# Microcontroller.net
KiCad netlist of a schematic drawn in Altium Designer
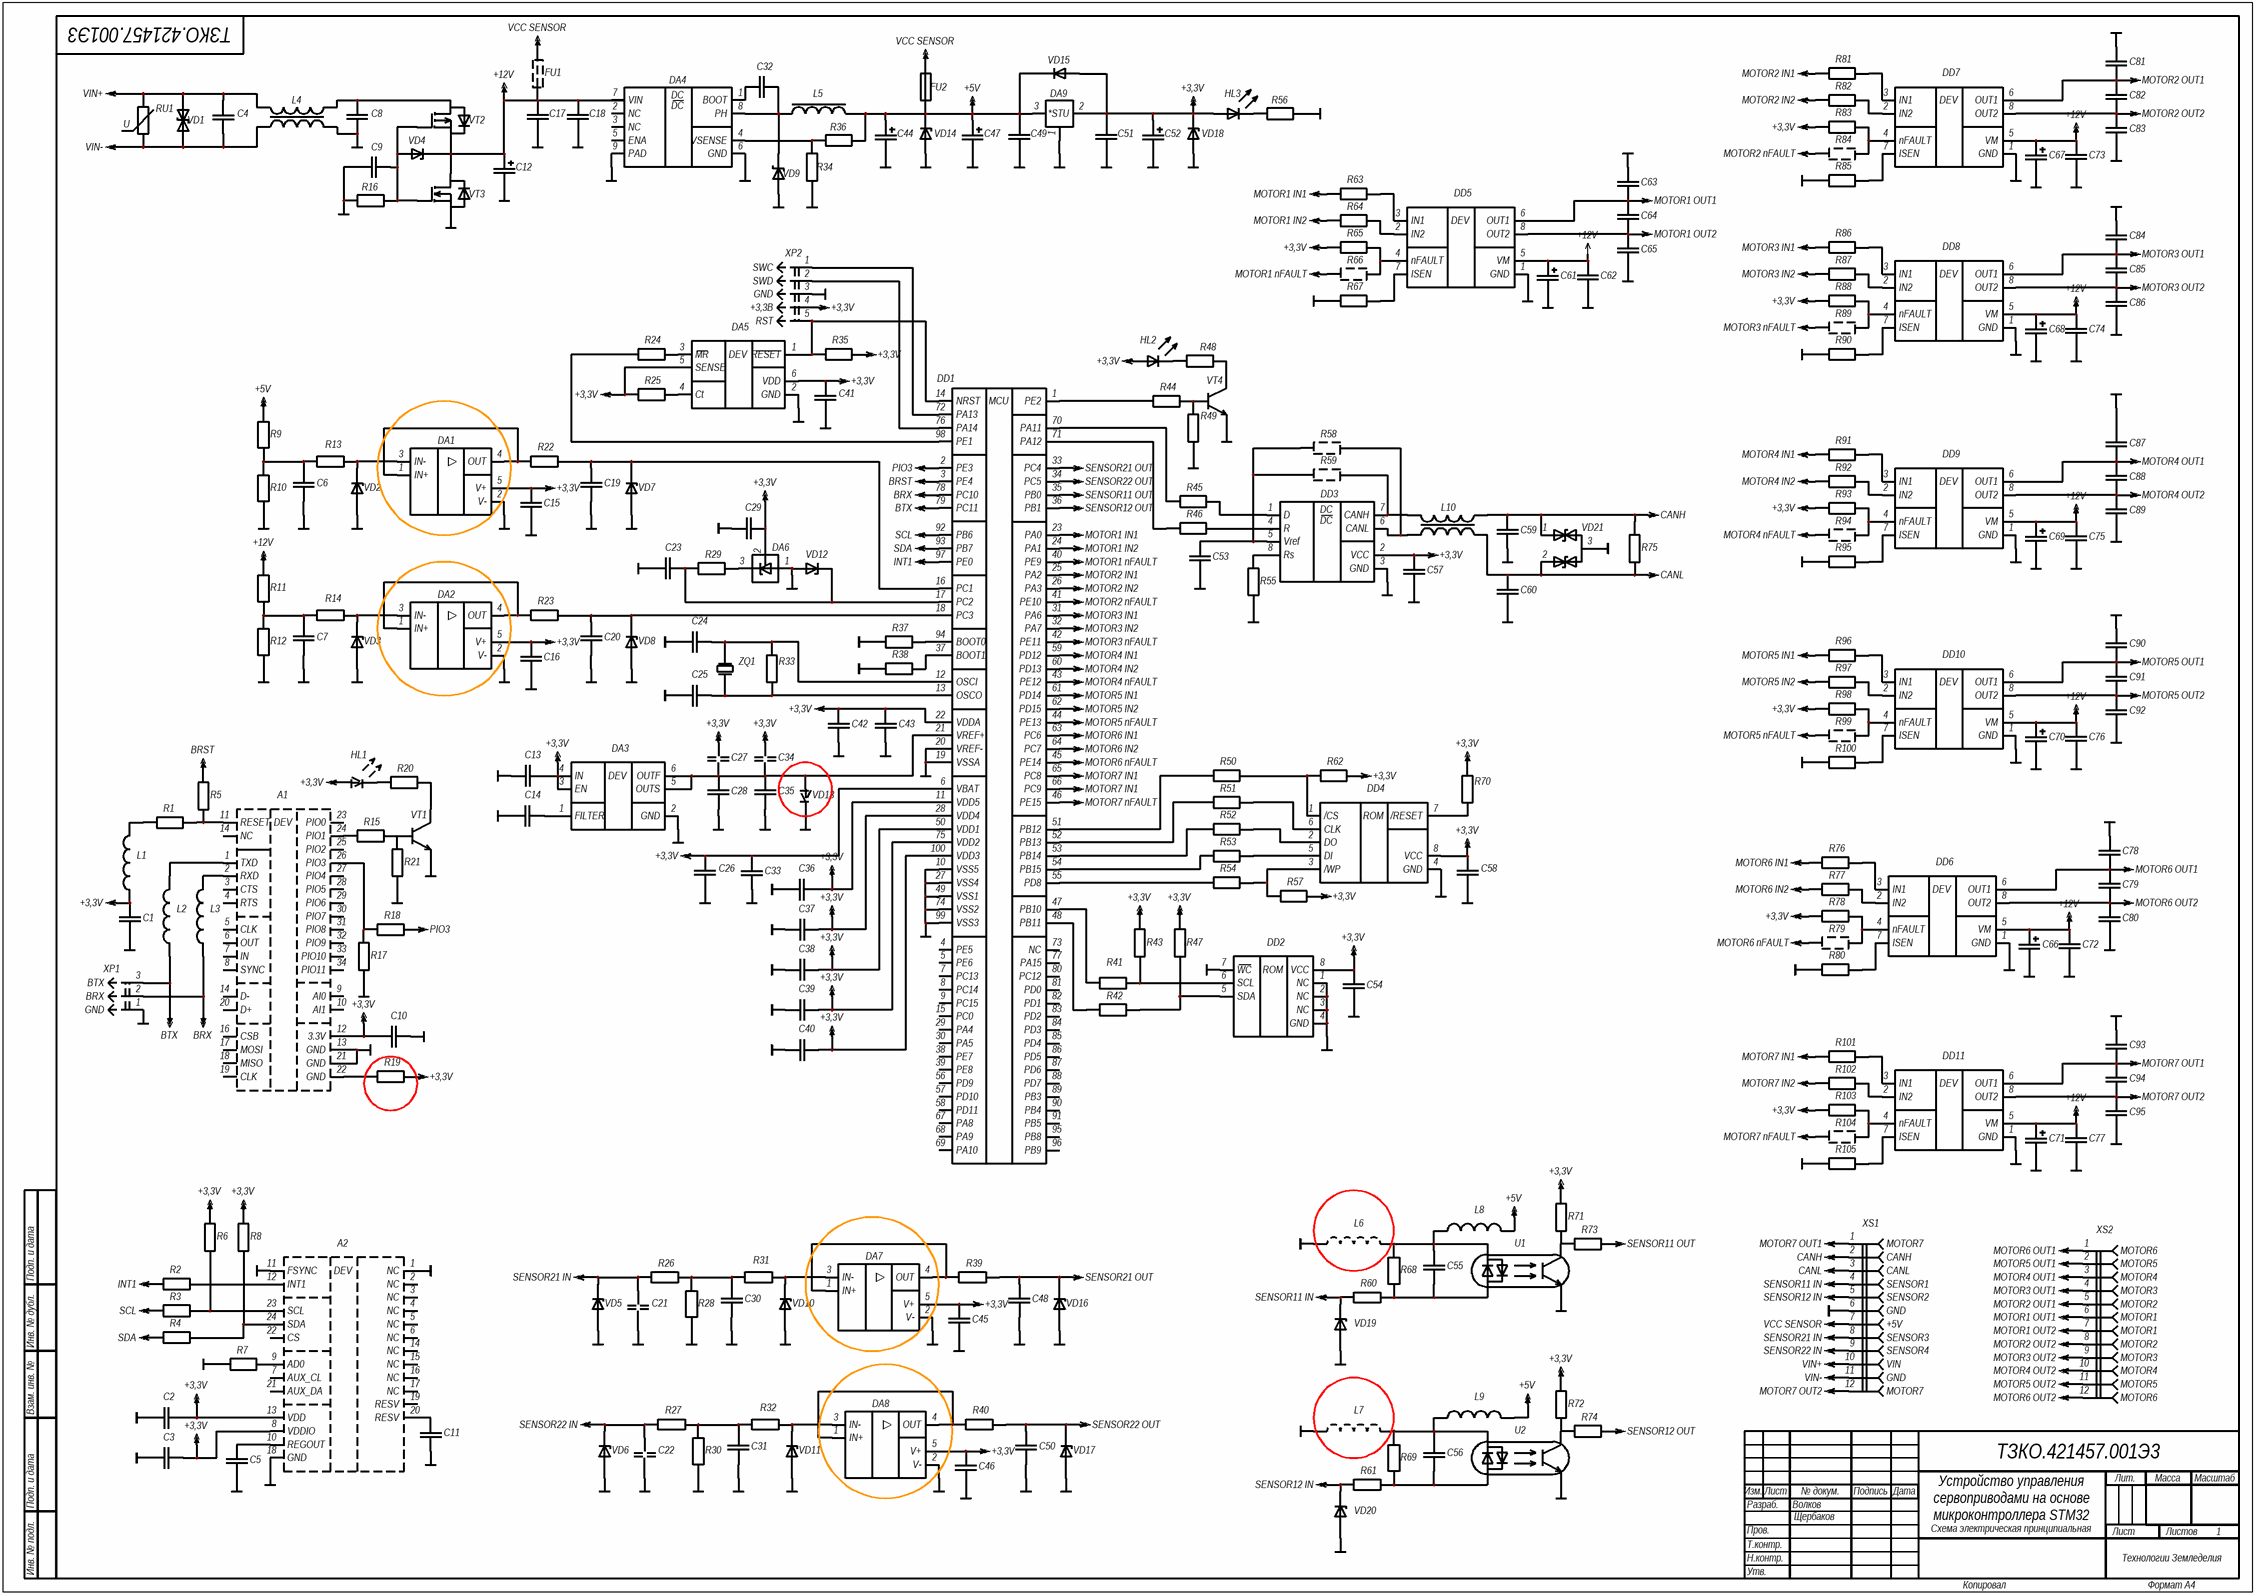
[diagram p0: Microcontroller.SchDoc]

(export (version "E")
  (design (tool "Eeschema 10.0.6"))
  (components
    (comp (ref "A1")
      (value "HC-06")
      (description "34 pin 3,3V not installed")
      (libsource (lib "Library") (part "Device_Bluetooth_HC-06_Not_Installed"))
    )
    (comp (ref "A2")
      (value "ICM-20948")
      (description "24 pin 3,3V not installed")
      (libsource (lib "Library") (part "Device_Gyroscope_Accelerometer_ICM-20948_Not_Installed"))
    )
    (comp (ref "C1")
      (value "Capacitor_Fixed")
      (description "2 pin")
      (libsource (lib "Library") (part "Capacitor_Fixed"))
    )
    (comp (ref "C2")
      (value "Capacitor_Fixed")
      (description "2 pin")
      (libsource (lib "Library") (part "Capacitor_Fixed"))
    )
    (comp (ref "C3")
      (value "Capacitor_Fixed")
      (description "2 pin")
      (libsource (lib "Library") (part "Capacitor_Fixed"))
    )
    (comp (ref "C4")
      (value "Capacitor_Fixed")
      (description "2 pin")
      (libsource (lib "Library") (part "Capacitor_Fixed"))
    )
    (comp (ref "C5")
      (value "Capacitor_Fixed")
      (description "2 pin")
      (libsource (lib "Library") (part "Capacitor_Fixed"))
    )
    (comp (ref "C6")
      (value "Capacitor_Fixed")
      (description "2 pin")
      (libsource (lib "Library") (part "Capacitor_Fixed"))
    )
    (comp (ref "C7")
      (value "Capacitor_Fixed")
      (description "2 pin")
      (libsource (lib "Library") (part "Capacitor_Fixed"))
    )
    (comp (ref "C8")
      (value "Capacitor_Fixed")
      (description "2 pin")
      (libsource (lib "Library") (part "Capacitor_Fixed"))
    )
    (comp (ref "C9")
      (value "Capacitor_Fixed")
      (description "2 pin")
      (libsource (lib "Library") (part "Capacitor_Fixed"))
    )
    (comp (ref "C10")
      (value "Capacitor_Fixed")
      (description "2 pin")
      (libsource (lib "Library") (part "Capacitor_Fixed"))
    )
    (comp (ref "C11")
      (value "Capacitor_Fixed")
      (description "2 pin")
      (libsource (lib "Library") (part "Capacitor_Fixed"))
    )
    (comp (ref "C12")
      (value "Capacitor_Polarized")
      (description "2 pin")
      (libsource (lib "Library") (part "Capacitor_Polarized"))
    )
    (comp (ref "C13")
      (value "Capacitor_Fixed")
      (description "2 pin")
      (libsource (lib "Library") (part "Capacitor_Fixed"))
    )
    (comp (ref "C14")
      (value "Capacitor_Fixed")
      (description "2 pin")
      (libsource (lib "Library") (part "Capacitor_Fixed"))
    )
    (comp (ref "C15")
      (value "Capacitor_Fixed")
      (description "2 pin")
      (libsource (lib "Library") (part "Capacitor_Fixed"))
    )
    (comp (ref "C16")
      (value "Capacitor_Fixed")
      (description "2 pin")
      (libsource (lib "Library") (part "Capacitor_Fixed"))
    )
    (comp (ref "C17")
      (value "Capacitor_Fixed")
      (description "2 pin")
      (libsource (lib "Library") (part "Capacitor_Fixed"))
    )
    (comp (ref "C18")
      (value "Capacitor_Fixed")
      (description "2 pin")
      (libsource (lib "Library") (part "Capacitor_Fixed"))
    )
    (comp (ref "C19")
      (value "Capacitor_Fixed")
      (description "2 pin")
      (libsource (lib "Library") (part "Capacitor_Fixed"))
    )
    (comp (ref "C20")
      (value "Capacitor_Fixed")
      (description "2 pin")
      (libsource (lib "Library") (part "Capacitor_Fixed"))
    )
    (comp (ref "C21")
      (value "Capacitor_Fixed_Not_Installed")
      (description "2 pin not installed")
      (libsource (lib "Library") (part "Capacitor_Fixed_Not_Installed"))
    )
    (comp (ref "C22")
      (value "Capacitor_Fixed_Not_Installed")
      (description "2 pin not installed")
      (libsource (lib "Library") (part "Capacitor_Fixed_Not_Installed"))
    )
    (comp (ref "C23")
      (value "Capacitor_Fixed")
      (description "2 pin")
      (libsource (lib "Library") (part "Capacitor_Fixed"))
    )
    (comp (ref "C24")
      (value "Capacitor_Fixed")
      (description "2 pin")
      (libsource (lib "Library") (part "Capacitor_Fixed"))
    )
    (comp (ref "C25")
      (value "Capacitor_Fixed")
      (description "2 pin")
      (libsource (lib "Library") (part "Capacitor_Fixed"))
    )
    (comp (ref "C26")
      (value "Capacitor_Fixed")
      (description "2 pin")
      (libsource (lib "Library") (part "Capacitor_Fixed"))
    )
    (comp (ref "C27")
      (value "Capacitor_Fixed_Not_Installed")
      (description "2 pin not installed")
      (libsource (lib "Library") (part "Capacitor_Fixed_Not_Installed"))
    )
    (comp (ref "C28")
      (value "Capacitor_Fixed")
      (description "2 pin")
      (libsource (lib "Library") (part "Capacitor_Fixed"))
    )
    (comp (ref "C29")
      (value "Capacitor_Fixed")
      (description "2 pin")
      (libsource (lib "Library") (part "Capacitor_Fixed"))
    )
    (comp (ref "C30")
      (value "Capacitor_Fixed")
      (description "2 pin")
      (libsource (lib "Library") (part "Capacitor_Fixed"))
    )
    (comp (ref "C31")
      (value "Capacitor_Fixed")
      (description "2 pin")
      (libsource (lib "Library") (part "Capacitor_Fixed"))
    )
    (comp (ref "C32")
      (value "Capacitor_Fixed")
      (description "2 pin")
      (libsource (lib "Library") (part "Capacitor_Fixed"))
    )
    (comp (ref "C33")
      (value "Capacitor_Fixed")
      (description "2 pin")
      (libsource (lib "Library") (part "Capacitor_Fixed"))
    )
    (comp (ref "C34")
      (value "Capacitor_Fixed_Not_Installed")
      (description "2 pin not installed")
      (libsource (lib "Library") (part "Capacitor_Fixed_Not_Installed"))
    )
    (comp (ref "C35")
      (value "Capacitor_Fixed")
      (description "2 pin")
      (libsource (lib "Library") (part "Capacitor_Fixed"))
    )
    (comp (ref "C36")
      (value "Capacitor_Fixed")
      (description "2 pin")
      (libsource (lib "Library") (part "Capacitor_Fixed"))
    )
    (comp (ref "C37")
      (value "Capacitor_Fixed")
      (description "2 pin")
      (libsource (lib "Library") (part "Capacitor_Fixed"))
    )
    (comp (ref "C38")
      (value "Capacitor_Fixed")
      (description "2 pin")
      (libsource (lib "Library") (part "Capacitor_Fixed"))
    )
    (comp (ref "C39")
      (value "Capacitor_Fixed")
      (description "2 pin")
      (libsource (lib "Library") (part "Capacitor_Fixed"))
    )
    (comp (ref "C40")
      (value "Capacitor_Fixed")
      (description "2 pin")
      (libsource (lib "Library") (part "Capacitor_Fixed"))
    )
    (comp (ref "C41")
      (value "Capacitor_Fixed")
      (description "2 pin")
      (libsource (lib "Library") (part "Capacitor_Fixed"))
    )
    (comp (ref "C42")
      (value "Capacitor_Fixed")
      (description "2 pin")
      (libsource (lib "Library") (part "Capacitor_Fixed"))
    )
    (comp (ref "C43")
      (value "Capacitor_Fixed")
      (description "2 pin")
      (libsource (lib "Library") (part "Capacitor_Fixed"))
    )
    (comp (ref "C44")
      (value "Capacitor_Polarized")
      (description "2 pin")
      (libsource (lib "Library") (part "Capacitor_Polarized"))
    )
    (comp (ref "C45")
      (value "Capacitor_Fixed")
      (description "2 pin")
      (libsource (lib "Library") (part "Capacitor_Fixed"))
    )
    (comp (ref "C46")
      (value "Capacitor_Fixed")
      (description "2 pin")
      (libsource (lib "Library") (part "Capacitor_Fixed"))
    )
    (comp (ref "C47")
      (value "Capacitor_Polarized")
      (description "2 pin")
      (libsource (lib "Library") (part "Capacitor_Polarized"))
    )
    (comp (ref "C48")
      (value "Capacitor_Fixed")
      (description "2 pin")
      (libsource (lib "Library") (part "Capacitor_Fixed"))
    )
    (comp (ref "C49")
      (value "Capacitor_Fixed")
      (description "2 pin")
      (libsource (lib "Library") (part "Capacitor_Fixed"))
    )
    (comp (ref "C50")
      (value "Capacitor_Fixed")
      (description "2 pin")
      (libsource (lib "Library") (part "Capacitor_Fixed"))
    )
    (comp (ref "C51")
      (value "Capacitor_Fixed")
      (description "2 pin")
      (libsource (lib "Library") (part "Capacitor_Fixed"))
    )
    (comp (ref "C52")
      (value "Capacitor_Polarized")
      (description "2 pin")
      (libsource (lib "Library") (part "Capacitor_Polarized"))
    )
    (comp (ref "C53")
      (value "Capacitor_Fixed")
      (description "2 pin")
      (libsource (lib "Library") (part "Capacitor_Fixed"))
    )
    (comp (ref "C54")
      (value "Capacitor_Fixed")
      (description "2 pin")
      (libsource (lib "Library") (part "Capacitor_Fixed"))
    )
    (comp (ref "C55")
      (value "Capacitor_Fixed")
      (description "2 pin")
      (libsource (lib "Library") (part "Capacitor_Fixed"))
    )
    (comp (ref "C56")
      (value "Capacitor_Fixed")
      (description "2 pin")
      (libsource (lib "Library") (part "Capacitor_Fixed"))
    )
    (comp (ref "C57")
      (value "Capacitor_Fixed")
      (description "2 pin")
      (libsource (lib "Library") (part "Capacitor_Fixed"))
    )
    (comp (ref "C58")
      (value "Capacitor_Fixed")
      (description "2 pin")
      (libsource (lib "Library") (part "Capacitor_Fixed"))
    )
    (comp (ref "C59")
      (value "Capacitor_Fixed")
      (description "2 pin")
      (libsource (lib "Library") (part "Capacitor_Fixed"))
    )
    (comp (ref "C60")
      (value "Capacitor_Fixed")
      (description "2 pin")
      (libsource (lib "Library") (part "Capacitor_Fixed"))
    )
    (comp (ref "C61")
      (value "Capacitor_Polarized")
      (description "2 pin")
      (libsource (lib "Library") (part "Capacitor_Polarized"))
    )
    (comp (ref "C62")
      (value "Capacitor_Fixed")
      (description "2 pin")
      (libsource (lib "Library") (part "Capacitor_Fixed"))
    )
    (comp (ref "C63")
      (value "Capacitor_Fixed")
      (description "2 pin")
      (libsource (lib "Library") (part "Capacitor_Fixed"))
    )
    (comp (ref "C64")
      (value "Capacitor_Fixed")
      (description "2 pin")
      (libsource (lib "Library") (part "Capacitor_Fixed"))
    )
    (comp (ref "C65")
      (value "Capacitor_Fixed")
      (description "2 pin")
      (libsource (lib "Library") (part "Capacitor_Fixed"))
    )
    (comp (ref "C66")
      (value "Capacitor_Polarized")
      (description "2 pin")
      (libsource (lib "Library") (part "Capacitor_Polarized"))
    )
    (comp (ref "C67")
      (value "Capacitor_Polarized")
      (description "2 pin")
      (libsource (lib "Library") (part "Capacitor_Polarized"))
    )
    (comp (ref "C68")
      (value "Capacitor_Polarized")
      (description "2 pin")
      (libsource (lib "Library") (part "Capacitor_Polarized"))
    )
    (comp (ref "C69")
      (value "Capacitor_Polarized")
      (description "2 pin")
      (libsource (lib "Library") (part "Capacitor_Polarized"))
    )
    (comp (ref "C70")
      (value "Capacitor_Polarized")
      (description "2 pin")
      (libsource (lib "Library") (part "Capacitor_Polarized"))
    )
    (comp (ref "C71")
      (value "Capacitor_Polarized")
      (description "2 pin")
      (libsource (lib "Library") (part "Capacitor_Polarized"))
    )
    (comp (ref "C72")
      (value "Capacitor_Fixed")
      (description "2 pin")
      (libsource (lib "Library") (part "Capacitor_Fixed"))
    )
    (comp (ref "C73")
      (value "Capacitor_Fixed")
      (description "2 pin")
      (libsource (lib "Library") (part "Capacitor_Fixed"))
    )
    (comp (ref "C74")
      (value "Capacitor_Fixed")
      (description "2 pin")
      (libsource (lib "Library") (part "Capacitor_Fixed"))
    )
    (comp (ref "C75")
      (value "Capacitor_Fixed")
      (description "2 pin")
      (libsource (lib "Library") (part "Capacitor_Fixed"))
    )
    (comp (ref "C76")
      (value "Capacitor_Fixed")
      (description "2 pin")
      (libsource (lib "Library") (part "Capacitor_Fixed"))
    )
    (comp (ref "C77")
      (value "Capacitor_Fixed")
      (description "2 pin")
      (libsource (lib "Library") (part "Capacitor_Fixed"))
    )
    (comp (ref "C78")
      (value "Capacitor_Fixed")
      (description "2 pin")
      (libsource (lib "Library") (part "Capacitor_Fixed"))
    )
    (comp (ref "C79")
      (value "Capacitor_Fixed")
      (description "2 pin")
      (libsource (lib "Library") (part "Capacitor_Fixed"))
    )
    (comp (ref "C80")
      (value "Capacitor_Fixed")
      (description "2 pin")
      (libsource (lib "Library") (part "Capacitor_Fixed"))
    )
    (comp (ref "C81")
      (value "Capacitor_Fixed")
      (description "2 pin")
      (libsource (lib "Library") (part "Capacitor_Fixed"))
    )
    (comp (ref "C82")
      (value "Capacitor_Fixed")
      (description "2 pin")
      (libsource (lib "Library") (part "Capacitor_Fixed"))
    )
    (comp (ref "C83")
      (value "Capacitor_Fixed")
      (description "2 pin")
      (libsource (lib "Library") (part "Capacitor_Fixed"))
    )
    (comp (ref "C84")
      (value "Capacitor_Fixed")
      (description "2 pin")
      (libsource (lib "Library") (part "Capacitor_Fixed"))
    )
    (comp (ref "C85")
      (value "Capacitor_Fixed")
      (description "2 pin")
      (libsource (lib "Library") (part "Capacitor_Fixed"))
    )
    (comp (ref "C86")
      (value "Capacitor_Fixed")
      (description "2 pin")
      (libsource (lib "Library") (part "Capacitor_Fixed"))
    )
    (comp (ref "C87")
      (value "Capacitor_Fixed")
      (description "2 pin")
      (libsource (lib "Library") (part "Capacitor_Fixed"))
    )
    (comp (ref "C88")
      (value "Capacitor_Fixed")
      (description "2 pin")
      (libsource (lib "Library") (part "Capacitor_Fixed"))
    )
    (comp (ref "C89")
      (value "Capacitor_Fixed")
      (description "2 pin")
      (libsource (lib "Library") (part "Capacitor_Fixed"))
    )
    (comp (ref "C90")
      (value "Capacitor_Fixed")
      (description "2 pin")
      (libsource (lib "Library") (part "Capacitor_Fixed"))
    )
    (comp (ref "C91")
      (value "Capacitor_Fixed")
      (description "2 pin")
      (libsource (lib "Library") (part "Capacitor_Fixed"))
    )
    (comp (ref "C92")
      (value "Capacitor_Fixed")
      (description "2 pin")
      (libsource (lib "Library") (part "Capacitor_Fixed"))
    )
    (comp (ref "C93")
      (value "Capacitor_Fixed")
      (description "2 pin")
      (libsource (lib "Library") (part "Capacitor_Fixed"))
    )
    (comp (ref "C94")
      (value "Capacitor_Fixed")
      (description "2 pin")
      (libsource (lib "Library") (part "Capacitor_Fixed"))
    )
    (comp (ref "C95")
      (value "Capacitor_Fixed")
      (description "2 pin")
      (libsource (lib "Library") (part "Capacitor_Fixed"))
    )
    (comp (ref "DA1")
      (value "OPA348AIDBVR")
      (description "5 pin 3,3V")
      (libsource (lib "Library") (part "Microcircuit_Analog_Operational_Amplifier_OPA348AIDBVR"))
    )
    (comp (ref "DA2")
      (value "OPA348AIDBVR")
      (description "5 pin 3,3V")
      (libsource (lib "Library") (part "Microcircuit_Analog_Operational_Amplifier_OPA348AIDBVR"))
    )
    (comp (ref "DA3")
      (value "MAX6070BAUT12+T")
      (description "6 pin 3,3V")
      (libsource (lib "Library") (part "Microcircuit_Analog_Reference_Voltage_Source_MAX6070BAUT12+T"))
    )
    (comp (ref "DA4")
      (value "TPS5430DDAR")
      (description "8 pin + pad from 12V to 5V")
      (libsource (lib "Library") (part "Microcircuit_Analog_DC_DC_Converter_TPS5430"))
    )
    (comp (ref "DA5")
      (value "TPS3808G33DBVR")
      (description "6 pin 3,3V")
      (libsource (lib "Library") (part "Microcircuit_Analog_Power_Monitor_TPS3808G33DBVR"))
    )
    (comp (ref "DA6")
      (value "TL431")
      (description "3 pin")
      (libsource (lib "Library") (part "Microcircuit_Analog_Reference_Power_Supply_TL431"))
    )
    (comp (ref "DA7")
      (value "OPA348AIDBVR")
      (description "5 pin 3,3V")
      (libsource (lib "Library") (part "Microcircuit_Analog_Operational_Amplifier_OPA348AIDBVR"))
    )
    (comp (ref "DA8")
      (value "OPA348AIDBVR")
      (description "5 pin 3,3V")
      (libsource (lib "Library") (part "Microcircuit_Analog_Operational_Amplifier_OPA348AIDBVR"))
    )
    (comp (ref "DA9")
      (value "LM1117MP")
      (description "3 pin from 5V to 3,3V")
      (libsource (lib "Library") (part "Microcircuit_Analog_Linear_Stabilizer_LM1117MP"))
    )
    (comp (ref "DD1")
      (value "STM32F103VET6")
      (description "100 pin 3,3V")
      (libsource (lib "Library") (part "Microcircuit_Digital_Microcontroller_STM32VET6"))
    )
    (comp (ref "DD2")
      (value "M24256E-FMN6TP")
      (description "8 pin 3,3V")
      (libsource (lib "Library") (part "Microcircuit_Digital_Memory_EEPROM_M24256E-FMN6TP"))
    )
    (comp (ref "DD3")
      (value "VP230")
      (description "8 pin 3,3V")
      (libsource (lib "Library") (part "Microcircuit_Digital_Transceiver_UART_CAN"))
    )
    (comp (ref "DD4")
      (value "W25Q64JVSSIQ")
      (description "8 pin 3,3V")
      (libsource (lib "Library") (part "Microcircuit_Digital_Memory_Flash_W25Q64JVSSIQ"))
    )
    (comp (ref "DD5")
      (value "AT8236")
      (description "8 pin 12V")
      (libsource (lib "Library") (part "Microcircuit_Digital_Motor_Driver_AT8236"))
    )
    (comp (ref "DD6")
      (value "AT8236")
      (description "8 pin 12V")
      (libsource (lib "Library") (part "Microcircuit_Digital_Motor_Driver_AT8236"))
    )
    (comp (ref "DD7")
      (value "AT8236")
      (description "8 pin 12V")
      (libsource (lib "Library") (part "Microcircuit_Digital_Motor_Driver_AT8236"))
    )
    (comp (ref "DD8")
      (value "AT8236")
      (description "8 pin 12V")
      (libsource (lib "Library") (part "Microcircuit_Digital_Motor_Driver_AT8236"))
    )
    (comp (ref "DD9")
      (value "AT8236")
      (description "8 pin 12V")
      (libsource (lib "Library") (part "Microcircuit_Digital_Motor_Driver_AT8236"))
    )
    (comp (ref "DD10")
      (value "AT8236")
      (description "8 pin 12V")
      (libsource (lib "Library") (part "Microcircuit_Digital_Motor_Driver_AT8236"))
    )
    (comp (ref "DD11")
      (value "AT8236")
      (description "8 pin 12V")
      (libsource (lib "Library") (part "Microcircuit_Digital_Motor_Driver_AT8236"))
    )
    (comp (ref "FU1")
      (value "Fuse_Not_Inctalled")
      (description "2 pin")
      (libsource (lib "Library") (part "Fuse_Not_Inctalled"))
    )
    (comp (ref "FU2") (value "Fuse") (description "2 pin") (libsource (lib "Library") (part "Fuse")))
    (comp (ref "HL1")
      (value "Diode_Light_Emitting_Not_Installed")
      (description "2 pin not installed")
      (libsource (lib "Library") (part "Diode_Light_Emitting_Not_Installed"))
    )
    (comp (ref "HL2")
      (value "Diode_Light_Emitting")
      (description "2 pin")
      (libsource (lib "Library") (part "Diode_Light_Emitting"))
    )
    (comp (ref "HL3")
      (value "Diode_Light_Emitting")
      (description "2 pin")
      (libsource (lib "Library") (part "Diode_Light_Emitting"))
    )
    (comp (ref "L1") (value "Inductor") (description "2 pin") (libsource (lib "Library") (part "Inductor")))
    (comp (ref "L2") (value "Inductor") (description "2 pin") (libsource (lib "Library") (part "Inductor")))
    (comp (ref "L3") (value "Inductor") (description "2 pin") (libsource (lib "Library") (part "Inductor")))
    (comp (ref "L4")
      (value "Inductor_Cored_Double")
      (description "4 pin")
      (libsource (lib "Library") (part "Inductor_Cored_Double"))
    )
    (comp (ref "L5")
      (value "Inductor_Cored")
      (description "2 pin")
      (libsource (lib "Library") (part "Inductor_Cored"))
    )
    (comp (ref "L6")
      (value "Inductor_Not_Installed")
      (description "2 pin not installed")
      (libsource (lib "Library") (part "Inductor_Not_Installed"))
    )
    (comp (ref "L7")
      (value "Inductor_Not_Installed")
      (description "2 pin not installed")
      (libsource (lib "Library") (part "Inductor_Not_Installed"))
    )
    (comp (ref "L8") (value "Inductor") (description "2 pin") (libsource (lib "Library") (part "Inductor")))
    (comp (ref "L9") (value "Inductor") (description "2 pin") (libsource (lib "Library") (part "Inductor")))
    (comp (ref "L10")
      (value "Inductor_Cored_Double")
      (description "4 pin")
      (libsource (lib "Library") (part "Inductor_Cored_Double"))
    )
    (comp (ref "R1")
      (value "Resistor_Fixed")
      (description "2 pin")
      (libsource (lib "Library") (part "Resistor_Fixed"))
    )
    (comp (ref "R2")
      (value "Resistor_Fixed")
      (description "2 pin")
      (libsource (lib "Library") (part "Resistor_Fixed"))
    )
    (comp (ref "R3")
      (value "Resistor_Fixed")
      (description "2 pin")
      (libsource (lib "Library") (part "Resistor_Fixed"))
    )
    (comp (ref "R4")
      (value "Resistor_Fixed")
      (description "2 pin")
      (libsource (lib "Library") (part "Resistor_Fixed"))
    )
    (comp (ref "R5")
      (value "Resistor_Fixed")
      (description "2 pin")
      (libsource (lib "Library") (part "Resistor_Fixed"))
    )
    (comp (ref "R6")
      (value "Resistor_Fixed")
      (description "2 pin")
      (libsource (lib "Library") (part "Resistor_Fixed"))
    )
    (comp (ref "R7")
      (value "Resistor_Fixed")
      (description "2 pin")
      (libsource (lib "Library") (part "Resistor_Fixed"))
    )
    (comp (ref "R8")
      (value "Resistor_Fixed")
      (description "2 pin")
      (libsource (lib "Library") (part "Resistor_Fixed"))
    )
    (comp (ref "R9")
      (value "Resistor_Fixed")
      (description "2 pin")
      (libsource (lib "Library") (part "Resistor_Fixed"))
    )
    (comp (ref "R10")
      (value "Resistor_Fixed")
      (description "2 pin")
      (libsource (lib "Library") (part "Resistor_Fixed"))
    )
    (comp (ref "R11")
      (value "Resistor_Fixed")
      (description "2 pin")
      (libsource (lib "Library") (part "Resistor_Fixed"))
    )
    (comp (ref "R12")
      (value "Resistor_Fixed")
      (description "2 pin")
      (libsource (lib "Library") (part "Resistor_Fixed"))
    )
    (comp (ref "R13")
      (value "Resistor_Fixed")
      (description "2 pin")
      (libsource (lib "Library") (part "Resistor_Fixed"))
    )
    (comp (ref "R14")
      (value "Resistor_Fixed")
      (description "2 pin")
      (libsource (lib "Library") (part "Resistor_Fixed"))
    )
    (comp (ref "R15")
      (value "Resistor_Fixed")
      (description "2 pin")
      (libsource (lib "Library") (part "Resistor_Fixed"))
    )
    (comp (ref "R16")
      (value "Resistor_Fixed")
      (description "2 pin")
      (libsource (lib "Library") (part "Resistor_Fixed"))
    )
    (comp (ref "R17")
      (value "Resistor_Fixed")
      (description "2 pin")
      (libsource (lib "Library") (part "Resistor_Fixed"))
    )
    (comp (ref "R18")
      (value "Resistor_Fixed")
      (description "2 pin")
      (libsource (lib "Library") (part "Resistor_Fixed"))
    )
    (comp (ref "R19")
      (value "Resistor_Fixed")
      (description "2 pin")
      (libsource (lib "Library") (part "Resistor_Fixed"))
    )
    (comp (ref "R20")
      (value "Resistor_Fixed")
      (description "2 pin")
      (libsource (lib "Library") (part "Resistor_Fixed"))
    )
    (comp (ref "R21")
      (value "Resistor_Fixed")
      (description "2 pin")
      (libsource (lib "Library") (part "Resistor_Fixed"))
    )
    (comp (ref "R22")
      (value "Resistor_Fixed")
      (description "2 pin")
      (libsource (lib "Library") (part "Resistor_Fixed"))
    )
    (comp (ref "R23")
      (value "Resistor_Fixed")
      (description "2 pin")
      (libsource (lib "Library") (part "Resistor_Fixed"))
    )
    (comp (ref "R24")
      (value "Resistor_Fixed")
      (description "2 pin")
      (libsource (lib "Library") (part "Resistor_Fixed"))
    )
    (comp (ref "R25")
      (value "Resistor_Fixed")
      (description "2 pin")
      (libsource (lib "Library") (part "Resistor_Fixed"))
    )
    (comp (ref "R26")
      (value "Resistor_Fixed")
      (description "2 pin")
      (libsource (lib "Library") (part "Resistor_Fixed"))
    )
    (comp (ref "R27")
      (value "Resistor_Fixed")
      (description "2 pin")
      (libsource (lib "Library") (part "Resistor_Fixed"))
    )
    (comp (ref "R28")
      (value "Resistor_Fixed")
      (description "2 pin")
      (libsource (lib "Library") (part "Resistor_Fixed"))
    )
    (comp (ref "R29")
      (value "Resistor_Fixed")
      (description "2 pin")
      (libsource (lib "Library") (part "Resistor_Fixed"))
    )
    (comp (ref "R30")
      (value "Resistor_Fixed")
      (description "2 pin")
      (libsource (lib "Library") (part "Resistor_Fixed"))
    )
    (comp (ref "R31")
      (value "Resistor_Fixed")
      (description "2 pin")
      (libsource (lib "Library") (part "Resistor_Fixed"))
    )
    (comp (ref "R32")
      (value "Resistor_Fixed")
      (description "2 pin")
      (libsource (lib "Library") (part "Resistor_Fixed"))
    )
    (comp (ref "R33")
      (value "Resistor_Fixed")
      (description "2 pin")
      (libsource (lib "Library") (part "Resistor_Fixed"))
    )
    (comp (ref "R34")
      (value "Resistor_Fixed")
      (description "2 pin")
      (libsource (lib "Library") (part "Resistor_Fixed"))
    )
    (comp (ref "R35")
      (value "Resistor_Fixed")
      (description "2 pin")
      (libsource (lib "Library") (part "Resistor_Fixed"))
    )
    (comp (ref "R36")
      (value "Resistor_Fixed")
      (description "2 pin")
      (libsource (lib "Library") (part "Resistor_Fixed"))
    )
    (comp (ref "R37")
      (value "Resistor_Fixed")
      (description "2 pin")
      (libsource (lib "Library") (part "Resistor_Fixed"))
    )
    (comp (ref "R38")
      (value "Resistor_Fixed")
      (description "2 pin")
      (libsource (lib "Library") (part "Resistor_Fixed"))
    )
    (comp (ref "R39")
      (value "Resistor_Fixed")
      (description "2 pin")
      (libsource (lib "Library") (part "Resistor_Fixed"))
    )
    (comp (ref "R40")
      (value "Resistor_Fixed")
      (description "2 pin")
      (libsource (lib "Library") (part "Resistor_Fixed"))
    )
    (comp (ref "R41")
      (value "Resistor_Fixed")
      (description "2 pin")
      (libsource (lib "Library") (part "Resistor_Fixed"))
    )
    (comp (ref "R42")
      (value "Resistor_Fixed")
      (description "2 pin")
      (libsource (lib "Library") (part "Resistor_Fixed"))
    )
    (comp (ref "R43")
      (value "Resistor_Fixed")
      (description "2 pin")
      (libsource (lib "Library") (part "Resistor_Fixed"))
    )
    (comp (ref "R44")
      (value "Resistor_Fixed")
      (description "2 pin")
      (libsource (lib "Library") (part "Resistor_Fixed"))
    )
    (comp (ref "R45")
      (value "Resistor_Fixed")
      (description "2 pin")
      (libsource (lib "Library") (part "Resistor_Fixed"))
    )
    (comp (ref "R46")
      (value "Resistor_Fixed")
      (description "2 pin")
      (libsource (lib "Library") (part "Resistor_Fixed"))
    )
    (comp (ref "R47")
      (value "Resistor_Fixed")
      (description "2 pin")
      (libsource (lib "Library") (part "Resistor_Fixed"))
    )
    (comp (ref "R48")
      (value "Resistor_Fixed")
      (description "2 pin")
      (libsource (lib "Library") (part "Resistor_Fixed"))
    )
    (comp (ref "R49")
      (value "Resistor_Fixed")
      (description "2 pin")
      (libsource (lib "Library") (part "Resistor_Fixed"))
    )
    (comp (ref "R50")
      (value "Resistor_Fixed")
      (description "2 pin")
      (libsource (lib "Library") (part "Resistor_Fixed"))
    )
    (comp (ref "R51")
      (value "Resistor_Fixed")
      (description "2 pin")
      (libsource (lib "Library") (part "Resistor_Fixed"))
    )
    (comp (ref "R52")
      (value "Resistor_Fixed")
      (description "2 pin")
      (libsource (lib "Library") (part "Resistor_Fixed"))
    )
    (comp (ref "R53")
      (value "Resistor_Fixed")
      (description "2 pin")
      (libsource (lib "Library") (part "Resistor_Fixed"))
    )
    (comp (ref "R54")
      (value "Resistor_Fixed")
      (description "2 pin")
      (libsource (lib "Library") (part "Resistor_Fixed"))
    )
    (comp (ref "R55")
      (value "Resistor_Fixed")
      (description "2 pin")
      (libsource (lib "Library") (part "Resistor_Fixed"))
    )
    (comp (ref "R56")
      (value "Resistor_Fixed")
      (description "2 pin")
      (libsource (lib "Library") (part "Resistor_Fixed"))
    )
    (comp (ref "R57")
      (value "Resistor_Fixed")
      (description "2 pin")
      (libsource (lib "Library") (part "Resistor_Fixed"))
    )
    (comp (ref "R58")
      (value "Resistor_Fixed_Not_Installed")
      (description "2 pin not installed")
      (libsource (lib "Library") (part "Resistor_Fixed_Not_Installed"))
    )
    (comp (ref "R59")
      (value "Resistor_Fixed_Not_Installed")
      (description "2 pin not installed")
      (libsource (lib "Library") (part "Resistor_Fixed_Not_Installed"))
    )
    (comp (ref "R60")
      (value "Resistor_Fixed")
      (description "2 pin")
      (libsource (lib "Library") (part "Resistor_Fixed"))
    )
    (comp (ref "R61")
      (value "Resistor_Fixed")
      (description "2 pin")
      (libsource (lib "Library") (part "Resistor_Fixed"))
    )
    (comp (ref "R62")
      (value "Resistor_Fixed")
      (description "2 pin")
      (libsource (lib "Library") (part "Resistor_Fixed"))
    )
    (comp (ref "R63")
      (value "Resistor_Fixed")
      (description "2 pin")
      (libsource (lib "Library") (part "Resistor_Fixed"))
    )
    (comp (ref "R64")
      (value "Resistor_Fixed")
      (description "2 pin")
      (libsource (lib "Library") (part "Resistor_Fixed"))
    )
    (comp (ref "R65")
      (value "Resistor_Fixed")
      (description "2 pin")
      (libsource (lib "Library") (part "Resistor_Fixed"))
    )
    (comp (ref "R66")
      (value "Resistor_Fixed_Not_Installed")
      (description "2 pin not installed")
      (libsource (lib "Library") (part "Resistor_Fixed_Not_Installed"))
    )
    (comp (ref "R67")
      (value "Resistor_Fixed")
      (description "2 pin")
      (libsource (lib "Library") (part "Resistor_Fixed"))
    )
    (comp (ref "R68")
      (value "Resistor_Fixed")
      (description "2 pin")
      (libsource (lib "Library") (part "Resistor_Fixed"))
    )
    (comp (ref "R69")
      (value "Resistor_Fixed")
      (description "2 pin")
      (libsource (lib "Library") (part "Resistor_Fixed"))
    )
    (comp (ref "R70")
      (value "Resistor_Fixed")
      (description "2 pin")
      (libsource (lib "Library") (part "Resistor_Fixed"))
    )
    (comp (ref "R71")
      (value "Resistor_Fixed")
      (description "2 pin")
      (libsource (lib "Library") (part "Resistor_Fixed"))
    )
    (comp (ref "R72")
      (value "Resistor_Fixed")
      (description "2 pin")
      (libsource (lib "Library") (part "Resistor_Fixed"))
    )
    (comp (ref "R73")
      (value "Resistor_Fixed")
      (description "2 pin")
      (libsource (lib "Library") (part "Resistor_Fixed"))
    )
    (comp (ref "R74")
      (value "Resistor_Fixed")
      (description "2 pin")
      (libsource (lib "Library") (part "Resistor_Fixed"))
    )
    (comp (ref "R75")
      (value "Resistor_Fixed")
      (description "2 pin")
      (libsource (lib "Library") (part "Resistor_Fixed"))
    )
    (comp (ref "R76")
      (value "Resistor_Fixed")
      (description "2 pin")
      (libsource (lib "Library") (part "Resistor_Fixed"))
    )
    (comp (ref "R77")
      (value "Resistor_Fixed")
      (description "2 pin")
      (libsource (lib "Library") (part "Resistor_Fixed"))
    )
    (comp (ref "R78")
      (value "Resistor_Fixed")
      (description "2 pin")
      (libsource (lib "Library") (part "Resistor_Fixed"))
    )
    (comp (ref "R79")
      (value "Resistor_Fixed_Not_Installed")
      (description "2 pin not installed")
      (libsource (lib "Library") (part "Resistor_Fixed_Not_Installed"))
    )
    (comp (ref "R80")
      (value "Resistor_Fixed")
      (description "2 pin")
      (libsource (lib "Library") (part "Resistor_Fixed"))
    )
    (comp (ref "R81")
      (value "Resistor_Fixed")
      (description "2 pin")
      (libsource (lib "Library") (part "Resistor_Fixed"))
    )
    (comp (ref "R82")
      (value "Resistor_Fixed")
      (description "2 pin")
      (libsource (lib "Library") (part "Resistor_Fixed"))
    )
    (comp (ref "R83")
      (value "Resistor_Fixed")
      (description "2 pin")
      (libsource (lib "Library") (part "Resistor_Fixed"))
    )
    (comp (ref "R84")
      (value "Resistor_Fixed_Not_Installed")
      (description "2 pin not installed")
      (libsource (lib "Library") (part "Resistor_Fixed_Not_Installed"))
    )
    (comp (ref "R85")
      (value "Resistor_Fixed")
      (description "2 pin")
      (libsource (lib "Library") (part "Resistor_Fixed"))
    )
    (comp (ref "R86")
      (value "Resistor_Fixed")
      (description "2 pin")
      (libsource (lib "Library") (part "Resistor_Fixed"))
    )
    (comp (ref "R87")
      (value "Resistor_Fixed")
      (description "2 pin")
      (libsource (lib "Library") (part "Resistor_Fixed"))
    )
    (comp (ref "R88")
      (value "Resistor_Fixed")
      (description "2 pin")
      (libsource (lib "Library") (part "Resistor_Fixed"))
    )
    (comp (ref "R89")
      (value "Resistor_Fixed_Not_Installed")
      (description "2 pin not installed")
      (libsource (lib "Library") (part "Resistor_Fixed_Not_Installed"))
    )
    (comp (ref "R90")
      (value "Resistor_Fixed")
      (description "2 pin")
      (libsource (lib "Library") (part "Resistor_Fixed"))
    )
    (comp (ref "R91")
      (value "Resistor_Fixed")
      (description "2 pin")
      (libsource (lib "Library") (part "Resistor_Fixed"))
    )
    (comp (ref "R92")
      (value "Resistor_Fixed")
      (description "2 pin")
      (libsource (lib "Library") (part "Resistor_Fixed"))
    )
    (comp (ref "R93")
      (value "Resistor_Fixed")
      (description "2 pin")
      (libsource (lib "Library") (part "Resistor_Fixed"))
    )
    (comp (ref "R94")
      (value "Resistor_Fixed_Not_Installed")
      (description "2 pin not installed")
      (libsource (lib "Library") (part "Resistor_Fixed_Not_Installed"))
    )
    (comp (ref "R95")
      (value "Resistor_Fixed")
      (description "2 pin")
      (libsource (lib "Library") (part "Resistor_Fixed"))
    )
    (comp (ref "R96")
      (value "Resistor_Fixed")
      (description "2 pin")
      (libsource (lib "Library") (part "Resistor_Fixed"))
    )
    (comp (ref "R97")
      (value "Resistor_Fixed")
      (description "2 pin")
      (libsource (lib "Library") (part "Resistor_Fixed"))
    )
    (comp (ref "R98")
      (value "Resistor_Fixed")
      (description "2 pin")
      (libsource (lib "Library") (part "Resistor_Fixed"))
    )
    (comp (ref "R99")
      (value "Resistor_Fixed_Not_Installed")
      (description "2 pin not installed")
      (libsource (lib "Library") (part "Resistor_Fixed_Not_Installed"))
    )
    (comp (ref "R100")
      (value "Resistor_Fixed")
      (description "2 pin")
      (libsource (lib "Library") (part "Resistor_Fixed"))
    )
    (comp (ref "R101")
      (value "Resistor_Fixed")
      (description "2 pin")
      (libsource (lib "Library") (part "Resistor_Fixed"))
    )
    (comp (ref "R102")
      (value "Resistor_Fixed")
      (description "2 pin")
      (libsource (lib "Library") (part "Resistor_Fixed"))
    )
    (comp (ref "R103")
      (value "Resistor_Fixed")
      (description "2 pin")
      (libsource (lib "Library") (part "Resistor_Fixed"))
    )
    (comp (ref "R104")
      (value "Resistor_Fixed_Not_Installed")
      (description "2 pin not installed")
      (libsource (lib "Library") (part "Resistor_Fixed_Not_Installed"))
    )
    (comp (ref "R105")
      (value "Resistor_Fixed")
      (description "2 pin")
      (libsource (lib "Library") (part "Resistor_Fixed"))
    )
    (comp (ref "RU1")
      (value "Resistor_Varistor")
      (description "2 pin")
      (libsource (lib "Library") (part "Resistor_Varistor"))
    )
    (comp (ref "U1")
      (value "EL3H4")
      (description "4 pin")
      (libsource (lib "Library") (part "Optocoupler_EL3H4"))
    )
    (comp (ref "U2")
      (value "EL3H4")
      (description "4 pin")
      (libsource (lib "Library") (part "Optocoupler_EL3H4"))
    )
    (comp (ref "VD1")
      (value "5.0SMDJ36CA")
      (description "2 pin")
      (libsource (lib "Library") (part "Diode_Suppressor_5.0SMDJ36CA"))
    )
    (comp (ref "VD2")
      (value "Diode_Zener")
      (description "2 pin")
      (libsource (lib "Library") (part "Diode_Zener"))
    )
    (comp (ref "VD3")
      (value "Diode_Zener")
      (description "2 pin")
      (libsource (lib "Library") (part "Diode_Zener"))
    )
    (comp (ref "VD4")
      (value "Diode_Zener")
      (description "2 pin")
      (libsource (lib "Library") (part "Diode_Zener"))
    )
    (comp (ref "VD5")
      (value "Diode_Zener")
      (description "2 pin")
      (libsource (lib "Library") (part "Diode_Zener"))
    )
    (comp (ref "VD6")
      (value "Diode_Zener")
      (description "2 pin")
      (libsource (lib "Library") (part "Diode_Zener"))
    )
    (comp (ref "VD7")
      (value "Diode_Zener")
      (description "2 pin")
      (libsource (lib "Library") (part "Diode_Zener"))
    )
    (comp (ref "VD8")
      (value "Diode_Zener")
      (description "2 pin")
      (libsource (lib "Library") (part "Diode_Zener"))
    )
    (comp (ref "VD9")
      (value "Diode_Schottky")
      (description "2 pin")
      (libsource (lib "Library") (part "Diode_Schottky"))
    )
    (comp (ref "VD10")
      (value "Diode_Zener")
      (description "2 pin")
      (libsource (lib "Library") (part "Diode_Zener"))
    )
    (comp (ref "VD11")
      (value "Diode_Zener")
      (description "2 pin")
      (libsource (lib "Library") (part "Diode_Zener"))
    )
    (comp (ref "VD12")
      (value "Diode_Zener")
      (description "2 pin")
      (libsource (lib "Library") (part "Diode_Zener"))
    )
    (comp (ref "VD13")
      (value "Diode_Junction_Not_Installed")
      (description "2 pin")
      (libsource (lib "Library") (part "Diode_Junction_Not_Installed"))
    )
    (comp (ref "VD14")
      (value "Diode_Zener")
      (description "2 pin")
      (libsource (lib "Library") (part "Diode_Zener"))
    )
    (comp (ref "VD15")
      (value "Diode_Junction")
      (description "2 pin")
      (libsource (lib "Library") (part "Diode_Junction"))
    )
    (comp (ref "VD16")
      (value "Diode_Zener")
      (description "2 pin")
      (libsource (lib "Library") (part "Diode_Zener"))
    )
    (comp (ref "VD17")
      (value "Diode_Zener")
      (description "2 pin")
      (libsource (lib "Library") (part "Diode_Zener"))
    )
    (comp (ref "VD18")
      (value "Diode_Zener")
      (description "2 pin")
      (libsource (lib "Library") (part "Diode_Zener"))
    )
    (comp (ref "VD19")
      (value "Diode_Zener")
      (description "2 pin")
      (libsource (lib "Library") (part "Diode_Zener"))
    )
    (comp (ref "VD20")
      (value "Diode_Zener")
      (description "2 pin")
      (libsource (lib "Library") (part "Diode_Zener"))
    )
    (comp (ref "VD21")
      (value "SM24CANB-02HTG")
      (description "3 pin")
      (libsource (lib "Library") (part "Diode_CAN_Array_Supressors_SM24CANB-02HTG"))
    )
    (comp (ref "VT1")
      (value "BC817")
      (description "3 pin")
      (libsource (lib "Library") (part "Transistor_Bipolar_NPN_BC817"))
    )
    (comp (ref "VT2")
      (value "STD35P6LLF6")
      (description "3 pin")
      (libsource (lib "Library") (part "Transistor_Field_Effect_P_Induced_Channel_STD35P6LLF6"))
    )
    (comp (ref "VT3")
      (value "FDB7030BL")
      (description "3 pin")
      (libsource (lib "Library") (part "Transistor_Field_Effect_N_Induced_Channel_FDB7030BL"))
    )
    (comp (ref "VT4")
      (value "BC817")
      (description "3 pin")
      (libsource (lib "Library") (part "Transistor_Bipolar_NPN_BC817"))
    )
    (comp (ref "XP1")
      (value "Connector_Bluetooth_Not_Installed")
      (description "3 pin not installed")
      (libsource (lib "Library") (part "Connector_Bluetooth_Not_Installed"))
    )
    (comp (ref "XP2")
      (value "Connector_STLink_Not_Installed")
      (description "5 pin not installed")
      (libsource (lib "Library") (part "Connector_STLink_Not_Installed"))
    )
    (comp (ref "XS1")
      (value "Connector_Left")
      (description "12 pin")
      (libsource (lib "Library") (part "Connector_Left"))
    )
    (comp (ref "XS2")
      (value "Connector_Right")
      (description "12 pin")
      (libsource (lib "Library") (part "Connector_Right"))
    )
    (comp (ref "ZQ1")
      (value "Quartz_Resonator")
      (description "2 pin")
      (libsource (lib "Library") (part "Quartz_Resonator"))
    )
  )
  (nets
    (net (code "1") (name "+3,3V") (class "Default")
      (node (ref "A1") (pin "12") (pinfunction "3.3V_12") (pintype "passive"))
      (node (ref "A2") (pin "13") (pinfunction "VDD_13") (pintype "passive"))
      (node (ref "A2") (pin "8") (pinfunction "VDDIO_8") (pintype "passive"))
      (node (ref "C1") (pin "2") (pinfunction "2_2") (pintype "passive"))
      (node (ref "C10") (pin "1") (pinfunction "1_1") (pintype "passive"))
      (node (ref "C13") (pin "1") (pinfunction "1_1") (pintype "passive"))
      (node (ref "C15") (pin "2") (pinfunction "2_2") (pintype "passive"))
      (node (ref "C16") (pin "2") (pinfunction "2_2") (pintype "passive"))
      (node (ref "C2") (pin "2") (pinfunction "2_2") (pintype "passive"))
      (node (ref "C26") (pin "2") (pinfunction "2_2") (pintype "passive"))
      (node (ref "C27") (pin "1") (pinfunction "1_1") (pintype "passive"))
      (node (ref "C29") (pin "1") (pinfunction "1_1") (pintype "passive"))
      (node (ref "C3") (pin "2") (pinfunction "2_2") (pintype "passive"))
      (node (ref "C33") (pin "1") (pinfunction "1_1") (pintype "passive"))
      (node (ref "C34") (pin "1") (pinfunction "1_1") (pintype "passive"))
      (node (ref "C36") (pin "2") (pinfunction "2_2") (pintype "passive"))
      (node (ref "C37") (pin "1") (pinfunction "1_1") (pintype "passive"))
      (node (ref "C38") (pin "1") (pinfunction "1_1") (pintype "passive"))
      (node (ref "C39") (pin "1") (pinfunction "1_1") (pintype "passive"))
      (node (ref "C40") (pin "1") (pinfunction "1_1") (pintype "passive"))
      (node (ref "C41") (pin "2") (pinfunction "2_2") (pintype "passive"))
      (node (ref "C42") (pin "1") (pinfunction "1_1") (pintype "passive"))
      (node (ref "C43") (pin "1") (pinfunction "1_1") (pintype "passive"))
      (node (ref "C45") (pin "2") (pinfunction "2_2") (pintype "passive"))
      (node (ref "C46") (pin "2") (pinfunction "2_2") (pintype "passive"))
      (node (ref "C51") (pin "2") (pinfunction "2_2") (pintype "passive"))
      (node (ref "C52") (pin "1") (pinfunction "Anode_1") (pintype "passive"))
      (node (ref "C54") (pin "2") (pinfunction "2_2") (pintype "passive"))
      (node (ref "C57") (pin "2") (pinfunction "2_2") (pintype "passive"))
      (node (ref "C58") (pin "2") (pinfunction "2_2") (pintype "passive"))
      (node (ref "DA1") (pin "5") (pinfunction "V+_5") (pintype "passive"))
      (node (ref "DA2") (pin "5") (pinfunction "V+_5") (pintype "passive"))
      (node (ref "DA3") (pin "3") (pinfunction "EN_3") (pintype "passive"))
      (node (ref "DA3") (pin "4") (pinfunction "IN_4") (pintype "passive"))
      (node (ref "DA5") (pin "5") (pinfunction "SENSE_5") (pintype "passive"))
      (node (ref "DA5") (pin "6") (pinfunction "VDD_6") (pintype "passive"))
      (node (ref "DA6") (pin "2") (pinfunction "Reference_2") (pintype "passive"))
      (node (ref "DA7") (pin "5") (pinfunction "V+_5") (pintype "passive"))
      (node (ref "DA8") (pin "5") (pinfunction "V+_5") (pintype "passive"))
      (node (ref "DA9") (pin "2") (pinfunction "VOUT_2") (pintype "passive"))
      (node (ref "DD1") (pin "100") (pinfunction "VDD3_100") (pintype "passive"))
      (node (ref "DD1") (pin "11") (pinfunction "VDD5_11") (pintype "passive"))
      (node (ref "DD1") (pin "22") (pinfunction "VDDA_22") (pintype "passive"))
      (node (ref "DD1") (pin "28") (pinfunction "VDD4_28") (pintype "passive"))
      (node (ref "DD1") (pin "50") (pinfunction "VDD1_50") (pintype "passive"))
      (node (ref "DD1") (pin "6") (pinfunction "VBAT_6") (pintype "passive"))
      (node (ref "DD1") (pin "75") (pinfunction "VDD2_75") (pintype "passive"))
      (node (ref "DD2") (pin "8") (pinfunction "VCC_8") (pintype "passive"))
      (node (ref "DD3") (pin "2") (pinfunction "VCC_2") (pintype "passive"))
      (node (ref "DD4") (pin "8") (pinfunction "VCC_8") (pintype "passive"))
      (node (ref "HL1") (pin "1") (pinfunction "Anode_1") (pintype "passive"))
      (node (ref "HL2") (pin "1") (pinfunction "Anode_1") (pintype "passive"))
      (node (ref "HL3") (pin "1") (pinfunction "Anode_1") (pintype "passive"))
      (node (ref "L1") (pin "1") (pinfunction "1_1") (pintype "passive"))
      (node (ref "R103") (pin "1") (pinfunction "1_1") (pintype "passive"))
      (node (ref "R19") (pin "1") (pinfunction "1_1") (pintype "passive"))
      (node (ref "R25") (pin "2") (pinfunction "2_2") (pintype "passive"))
      (node (ref "R35") (pin "2") (pinfunction "2_2") (pintype "passive"))
      (node (ref "R43") (pin "2") (pinfunction "2_2") (pintype "passive"))
      (node (ref "R47") (pin "2") (pinfunction "2_2") (pintype "passive"))
      (node (ref "R57") (pin "2") (pinfunction "2_2") (pintype "passive"))
      (node (ref "R6") (pin "2") (pinfunction "2_2") (pintype "passive"))
      (node (ref "R62") (pin "2") (pinfunction "2_2") (pintype "passive"))
      (node (ref "R65") (pin "1") (pinfunction "1_1") (pintype "passive"))
      (node (ref "R70") (pin "2") (pinfunction "2_2") (pintype "passive"))
      (node (ref "R71") (pin "1") (pinfunction "1_1") (pintype "passive"))
      (node (ref "R72") (pin "1") (pinfunction "1_1") (pintype "passive"))
      (node (ref "R78") (pin "1") (pinfunction "1_1") (pintype "passive"))
      (node (ref "R8") (pin "2") (pinfunction "2_2") (pintype "passive"))
      (node (ref "R83") (pin "1") (pinfunction "1_1") (pintype "passive"))
      (node (ref "R88") (pin "1") (pinfunction "1_1") (pintype "passive"))
      (node (ref "R93") (pin "1") (pinfunction "1_1") (pintype "passive"))
      (node (ref "R98") (pin "1") (pinfunction "1_1") (pintype "passive"))
      (node (ref "VD15") (pin "1") (pinfunction "Anode_1") (pintype "passive"))
      (node (ref "VD18") (pin "2") (pinfunction "Cathode_2") (pintype "passive"))
      (node (ref "XP2") (pin "4") (pinfunction "+3,3В_4") (pintype "passive"))
    )
    (net (code "2") (name "+5V") (class "Default")
      (node (ref "C44") (pin "1") (pinfunction "Anode_1") (pintype "passive"))
      (node (ref "C47") (pin "1") (pinfunction "Anode_1") (pintype "passive"))
      (node (ref "C49") (pin "2") (pinfunction "2_2") (pintype "passive"))
      (node (ref "DA9") (pin "3") (pinfunction "VIN_3") (pintype "passive"))
      (node (ref "FU2") (pin "1") (pinfunction "1_1") (pintype "passive"))
      (node (ref "L5") (pin "2") (pinfunction "2_2") (pintype "passive"))
      (node (ref "L8") (pin "2") (pinfunction "2_2") (pintype "passive"))
      (node (ref "L9") (pin "2") (pinfunction "2_2") (pintype "passive"))
      (node (ref "R36") (pin "2") (pinfunction "2_2") (pintype "passive"))
      (node (ref "R9") (pin "1") (pinfunction "1_1") (pintype "passive"))
      (node (ref "VD14") (pin "2") (pinfunction "Cathode_2") (pintype "passive"))
      (node (ref "VD15") (pin "2") (pinfunction "Cathode_2") (pintype "passive"))
    )
    (net (code "3") (name "+12V") (class "Default")
      (node (ref "C12") (pin "1") (pinfunction "Anode_1") (pintype "passive"))
      (node (ref "C17") (pin "2") (pinfunction "2_2") (pintype "passive"))
      (node (ref "C18") (pin "2") (pinfunction "2_2") (pintype "passive"))
      (node (ref "C61") (pin "1") (pinfunction "Anode_1") (pintype "passive"))
      (node (ref "C62") (pin "2") (pinfunction "2_2") (pintype "passive"))
      (node (ref "C66") (pin "1") (pinfunction "Anode_1") (pintype "passive"))
      (node (ref "C67") (pin "1") (pinfunction "Anode_1") (pintype "passive"))
      (node (ref "C68") (pin "1") (pinfunction "Anode_1") (pintype "passive"))
      (node (ref "C69") (pin "1") (pinfunction "Anode_1") (pintype "passive"))
      (node (ref "C70") (pin "1") (pinfunction "Anode_1") (pintype "passive"))
      (node (ref "C71") (pin "1") (pinfunction "Anode_1") (pintype "passive"))
      (node (ref "C72") (pin "2") (pinfunction "2_2") (pintype "passive"))
      (node (ref "C73") (pin "2") (pinfunction "2_2") (pintype "passive"))
      (node (ref "C74") (pin "2") (pinfunction "2_2") (pintype "passive"))
      (node (ref "C75") (pin "2") (pinfunction "2_2") (pintype "passive"))
      (node (ref "C76") (pin "2") (pinfunction "2_2") (pintype "passive"))
      (node (ref "C77") (pin "2") (pinfunction "2_2") (pintype "passive"))
      (node (ref "DA4") (pin "7") (pinfunction "VIN_7") (pintype "passive"))
      (node (ref "DD10") (pin "5") (pinfunction "VM_5") (pintype "passive"))
      (node (ref "DD11") (pin "5") (pinfunction "VM_5") (pintype "passive"))
      (node (ref "DD5") (pin "5") (pinfunction "VM_5") (pintype "passive"))
      (node (ref "DD6") (pin "5") (pinfunction "VM_5") (pintype "passive"))
      (node (ref "DD7") (pin "5") (pinfunction "VM_5") (pintype "passive"))
      (node (ref "DD8") (pin "5") (pinfunction "VM_5") (pintype "passive"))
      (node (ref "DD9") (pin "5") (pinfunction "VM_5") (pintype "passive"))
      (node (ref "FU1") (pin "1") (pinfunction "1_1") (pintype "passive"))
      (node (ref "R11") (pin "1") (pinfunction "1_1") (pintype "passive"))
      (node (ref "VD4") (pin "2") (pinfunction "Cathode_2") (pintype "passive"))
      (node (ref "VT2") (pin "2") (pinfunction "Source_2") (pintype "passive"))
      (node (ref "VT3") (pin "3") (pinfunction "Drain_3") (pintype "passive"))
    )
    (net (code "4") (name "BRST") (class "Default")
      (node (ref "DD1") (pin "3") (pinfunction "PE4_3") (pintype "passive"))
      (node (ref "R5") (pin "2") (pinfunction "2_2") (pintype "passive"))
    )
    (net (code "5") (name "BRX") (class "Default")
      (node (ref "DD1") (pin "78") (pinfunction "PC10_78") (pintype "passive"))
      (node (ref "L3") (pin "1") (pinfunction "1_1") (pintype "passive"))
      (node (ref "XP1") (pin "2") (pinfunction "BRX_2") (pintype "passive"))
    )
    (net (code "6") (name "BTX") (class "Default")
      (node (ref "DD1") (pin "79") (pinfunction "PC11_79") (pintype "passive"))
      (node (ref "L2") (pin "1") (pinfunction "1_1") (pintype "passive"))
      (node (ref "XP1") (pin "3") (pinfunction "BTX_3") (pintype "passive"))
    )
    (net (code "7") (name "CANH") (class "Default")
      (node (ref "C59") (pin "1") (pinfunction "1_1") (pintype "passive"))
      (node (ref "L10") (pin "4") (pinfunction "4_4") (pintype "passive"))
      (node (ref "R75") (pin "2") (pinfunction "2_2") (pintype "passive"))
      (node (ref "VD21") (pin "1") (pinfunction "CANH_1") (pintype "passive"))
      (node (ref "XS1") (pin "2") (pinfunction "CANH_2") (pintype "passive"))
    )
    (net (code "8") (name "CANL") (class "Default")
      (node (ref "C60") (pin "2") (pinfunction "2_2") (pintype "passive"))
      (node (ref "L10") (pin "3") (pinfunction "3_3") (pintype "passive"))
      (node (ref "R75") (pin "1") (pinfunction "1_1") (pintype "passive"))
      (node (ref "VD21") (pin "2") (pinfunction "CANL_2") (pintype "passive"))
      (node (ref "XS1") (pin "3") (pinfunction "CANL_3") (pintype "passive"))
    )
    (net (code "9") (name "GND") (class "Default")
      (node (ref "A1") (pin "13") (pinfunction "GND_13") (pintype "passive"))
      (node (ref "A1") (pin "21") (pinfunction "GND_21") (pintype "passive"))
      (node (ref "A2") (pin "1") (pinfunction "NC_1") (pintype "passive"))
      (node (ref "A2") (pin "11") (pinfunction "FSYNC_11") (pintype "passive"))
      (node (ref "A2") (pin "18") (pinfunction "GND_18") (pintype "passive"))
      (node (ref "C1") (pin "1") (pinfunction "1_1") (pintype "passive"))
      (node (ref "C10") (pin "2") (pinfunction "2_2") (pintype "passive"))
      (node (ref "C11") (pin "2") (pinfunction "2_2") (pintype "passive"))
      (node (ref "C12") (pin "2") (pinfunction "Cathode_2") (pintype "passive"))
      (node (ref "C13") (pin "2") (pinfunction "2_2") (pintype "passive"))
      (node (ref "C14") (pin "1") (pinfunction "1_1") (pintype "passive"))
      (node (ref "C15") (pin "1") (pinfunction "1_1") (pintype "passive"))
      (node (ref "C16") (pin "1") (pinfunction "1_1") (pintype "passive"))
      (node (ref "C17") (pin "1") (pinfunction "1_1") (pintype "passive"))
      (node (ref "C18") (pin "1") (pinfunction "1_1") (pintype "passive"))
      (node (ref "C19") (pin "1") (pinfunction "1_1") (pintype "passive"))
      (node (ref "C2") (pin "1") (pinfunction "1_1") (pintype "passive"))
      (node (ref "C20") (pin "1") (pinfunction "1_1") (pintype "passive"))
      (node (ref "C21") (pin "1") (pinfunction "1_1") (pintype "passive"))
      (node (ref "C22") (pin "1") (pinfunction "1_1") (pintype "passive"))
      (node (ref "C23") (pin "1") (pinfunction "1_1") (pintype "passive"))
      (node (ref "C24") (pin "1") (pinfunction "1_1") (pintype "passive"))
      (node (ref "C25") (pin "1") (pinfunction "1_1") (pintype "passive"))
      (node (ref "C26") (pin "1") (pinfunction "1_1") (pintype "passive"))
      (node (ref "C28") (pin "1") (pinfunction "1_1") (pintype "passive"))
      (node (ref "C29") (pin "2") (pinfunction "2_2") (pintype "passive"))
      (node (ref "C3") (pin "1") (pinfunction "1_1") (pintype "passive"))
      (node (ref "C30") (pin "1") (pinfunction "1_1") (pintype "passive"))
      (node (ref "C31") (pin "1") (pinfunction "1_1") (pintype "passive"))
      (node (ref "C33") (pin "2") (pinfunction "2_2") (pintype "passive"))
      (node (ref "C35") (pin "1") (pinfunction "1_1") (pintype "passive"))
      (node (ref "C36") (pin "1") (pinfunction "1_1") (pintype "passive"))
      (node (ref "C37") (pin "2") (pinfunction "2_2") (pintype "passive"))
      (node (ref "C38") (pin "2") (pinfunction "2_2") (pintype "passive"))
      (node (ref "C39") (pin "2") (pinfunction "2_2") (pintype "passive"))
      (node (ref "C40") (pin "2") (pinfunction "2_2") (pintype "passive"))
      (node (ref "C41") (pin "1") (pinfunction "1_1") (pintype "passive"))
      (node (ref "C42") (pin "2") (pinfunction "2_2") (pintype "passive"))
      (node (ref "C43") (pin "2") (pinfunction "2_2") (pintype "passive"))
      (node (ref "C44") (pin "2") (pinfunction "Cathode_2") (pintype "passive"))
      (node (ref "C45") (pin "1") (pinfunction "1_1") (pintype "passive"))
      (node (ref "C46") (pin "1") (pinfunction "1_1") (pintype "passive"))
      (node (ref "C47") (pin "2") (pinfunction "Cathode_2") (pintype "passive"))
      (node (ref "C48") (pin "1") (pinfunction "1_1") (pintype "passive"))
      (node (ref "C49") (pin "1") (pinfunction "1_1") (pintype "passive"))
      (node (ref "C5") (pin "1") (pinfunction "1_1") (pintype "passive"))
      (node (ref "C50") (pin "1") (pinfunction "1_1") (pintype "passive"))
      (node (ref "C51") (pin "1") (pinfunction "1_1") (pintype "passive"))
      (node (ref "C52") (pin "2") (pinfunction "Cathode_2") (pintype "passive"))
      (node (ref "C53") (pin "1") (pinfunction "1_1") (pintype "passive"))
      (node (ref "C54") (pin "1") (pinfunction "1_1") (pintype "passive"))
      (node (ref "C57") (pin "1") (pinfunction "1_1") (pintype "passive"))
      (node (ref "C58") (pin "1") (pinfunction "1_1") (pintype "passive"))
      (node (ref "C59") (pin "2") (pinfunction "2_2") (pintype "passive"))
      (node (ref "C6") (pin "1") (pinfunction "1_1") (pintype "passive"))
      (node (ref "C60") (pin "1") (pinfunction "1_1") (pintype "passive"))
      (node (ref "C61") (pin "2") (pinfunction "Cathode_2") (pintype "passive"))
      (node (ref "C62") (pin "1") (pinfunction "1_1") (pintype "passive"))
      (node (ref "C63") (pin "2") (pinfunction "2_2") (pintype "passive"))
      (node (ref "C65") (pin "1") (pinfunction "1_1") (pintype "passive"))
      (node (ref "C66") (pin "2") (pinfunction "Cathode_2") (pintype "passive"))
      (node (ref "C67") (pin "2") (pinfunction "Cathode_2") (pintype "passive"))
      (node (ref "C68") (pin "2") (pinfunction "Cathode_2") (pintype "passive"))
      (node (ref "C69") (pin "2") (pinfunction "Cathode_2") (pintype "passive"))
      (node (ref "C7") (pin "1") (pinfunction "1_1") (pintype "passive"))
      (node (ref "C70") (pin "2") (pinfunction "Cathode_2") (pintype "passive"))
      (node (ref "C71") (pin "2") (pinfunction "Cathode_2") (pintype "passive"))
      (node (ref "C72") (pin "1") (pinfunction "1_1") (pintype "passive"))
      (node (ref "C73") (pin "1") (pinfunction "1_1") (pintype "passive"))
      (node (ref "C74") (pin "1") (pinfunction "1_1") (pintype "passive"))
      (node (ref "C75") (pin "1") (pinfunction "1_1") (pintype "passive"))
      (node (ref "C76") (pin "1") (pinfunction "1_1") (pintype "passive"))
      (node (ref "C77") (pin "1") (pinfunction "1_1") (pintype "passive"))
      (node (ref "C78") (pin "2") (pinfunction "2_2") (pintype "passive"))
      (node (ref "C8") (pin "1") (pinfunction "1_1") (pintype "passive"))
      (node (ref "C80") (pin "1") (pinfunction "1_1") (pintype "passive"))
      (node (ref "C81") (pin "2") (pinfunction "2_2") (pintype "passive"))
      (node (ref "C83") (pin "1") (pinfunction "1_1") (pintype "passive"))
      (node (ref "C84") (pin "2") (pinfunction "2_2") (pintype "passive"))
      (node (ref "C86") (pin "1") (pinfunction "1_1") (pintype "passive"))
      (node (ref "C87") (pin "2") (pinfunction "2_2") (pintype "passive"))
      (node (ref "C89") (pin "1") (pinfunction "1_1") (pintype "passive"))
      (node (ref "C9") (pin "1") (pinfunction "1_1") (pintype "passive"))
      (node (ref "C90") (pin "2") (pinfunction "2_2") (pintype "passive"))
      (node (ref "C92") (pin "1") (pinfunction "1_1") (pintype "passive"))
      (node (ref "C93") (pin "2") (pinfunction "2_2") (pintype "passive"))
      (node (ref "C95") (pin "1") (pinfunction "1_1") (pintype "passive"))
      (node (ref "DA1") (pin "2") (pinfunction "V-_2") (pintype "passive"))
      (node (ref "DA2") (pin "2") (pinfunction "V-_2") (pintype "passive"))
      (node (ref "DA3") (pin "2") (pinfunction "GND_2") (pintype "passive"))
      (node (ref "DA4") (pin "6") (pinfunction "GND_6") (pintype "passive"))
      (node (ref "DA4") (pin "9") (pinfunction "PAD_9") (pintype "passive"))
      (node (ref "DA5") (pin "2") (pinfunction "GND_2") (pintype "passive"))
      (node (ref "DA6") (pin "1") (pinfunction "Cathode_1") (pintype "passive"))
      (node (ref "DA7") (pin "2") (pinfunction "V-_2") (pintype "passive"))
      (node (ref "DA8") (pin "2") (pinfunction "V-_2") (pintype "passive"))
      (node (ref "DA9") (pin "1") (pinfunction "GND_1") (pintype "passive"))
      (node (ref "DD1") (pin "10") (pinfunction "VSS5_10") (pintype "passive"))
      (node (ref "DD1") (pin "19") (pinfunction "VSSA_19") (pintype "passive"))
      (node (ref "DD1") (pin "20") (pinfunction "VREF-_20") (pintype "passive"))
      (node (ref "DD1") (pin "27") (pinfunction "VSS4_27") (pintype "passive"))
      (node (ref "DD1") (pin "49") (pinfunction "VSS1_49") (pintype "passive"))
      (node (ref "DD1") (pin "74") (pinfunction "VSS2_74") (pintype "passive"))
      (node (ref "DD1") (pin "99") (pinfunction "VSS3_99") (pintype "passive"))
      (node (ref "DD10") (pin "1") (pinfunction "GND_1") (pintype "passive"))
      (node (ref "DD11") (pin "1") (pinfunction "GND_1") (pintype "passive"))
      (node (ref "DD2") (pin "1") (pinfunction "NC_1") (pintype "passive"))
      (node (ref "DD2") (pin "2") (pinfunction "NC_2") (pintype "passive"))
      (node (ref "DD2") (pin "3") (pinfunction "NC_3") (pintype "passive"))
      (node (ref "DD2") (pin "4") (pinfunction "GND_4") (pintype "passive"))
      (node (ref "DD2") (pin "7") (pinfunction "WC_7") (pintype "passive"))
      (node (ref "DD3") (pin "3") (pinfunction "GND_3") (pintype "passive"))
      (node (ref "DD4") (pin "4") (pinfunction "GND_4") (pintype "passive"))
      (node (ref "DD5") (pin "1") (pinfunction "GND_1") (pintype "passive"))
      (node (ref "DD6") (pin "1") (pinfunction "GND_1") (pintype "passive"))
      (node (ref "DD7") (pin "1") (pinfunction "GND_1") (pintype "passive"))
      (node (ref "DD8") (pin "1") (pinfunction "GND_1") (pintype "passive"))
      (node (ref "DD9") (pin "1") (pinfunction "GND_1") (pintype "passive"))
      (node (ref "L4") (pin "3") (pinfunction "3_3") (pintype "passive"))
      (node (ref "L6") (pin "1") (pinfunction "1_1") (pintype "passive"))
      (node (ref "R10") (pin "2") (pinfunction "2_2") (pintype "passive"))
      (node (ref "R100") (pin "1") (pinfunction "1_1") (pintype "passive"))
      (node (ref "R105") (pin "1") (pinfunction "1_1") (pintype "passive"))
      (node (ref "R12") (pin "2") (pinfunction "2_2") (pintype "passive"))
      (node (ref "R16") (pin "1") (pinfunction "1_1") (pintype "passive"))
      (node (ref "R17") (pin "1") (pinfunction "1_1") (pintype "passive"))
      (node (ref "R21") (pin "1") (pinfunction "1_1") (pintype "passive"))
      (node (ref "R28") (pin "2") (pinfunction "2_2") (pintype "passive"))
      (node (ref "R30") (pin "2") (pinfunction "2_2") (pintype "passive"))
      (node (ref "R34") (pin "1") (pinfunction "1_1") (pintype "passive"))
      (node (ref "R37") (pin "1") (pinfunction "1_1") (pintype "passive"))
      (node (ref "R38") (pin "1") (pinfunction "1_1") (pintype "passive"))
      (node (ref "R49") (pin "1") (pinfunction "1_1") (pintype "passive"))
      (node (ref "R55") (pin "1") (pinfunction "1_1") (pintype "passive"))
      (node (ref "R56") (pin "2") (pinfunction "2_2") (pintype "passive"))
      (node (ref "R67") (pin "1") (pinfunction "1_1") (pintype "passive"))
      (node (ref "R7") (pin "1") (pinfunction "1_1") (pintype "passive"))
      (node (ref "R80") (pin "1") (pinfunction "1_1") (pintype "passive"))
      (node (ref "R85") (pin "1") (pinfunction "1_1") (pintype "passive"))
      (node (ref "R90") (pin "1") (pinfunction "1_1") (pintype "passive"))
      (node (ref "R95") (pin "1") (pinfunction "1_1") (pintype "passive"))
      (node (ref "U1") (pin "3") (pinfunction "3_3") (pintype "passive"))
      (node (ref "U2") (pin "3") (pinfunction "3_3") (pintype "passive"))
      (node (ref "VD10") (pin "1") (pinfunction "Anode_1") (pintype "passive"))
      (node (ref "VD11") (pin "1") (pinfunction "Anode_1") (pintype "passive"))
      (node (ref "VD12") (pin "1") (pinfunction "Anode_1") (pintype "passive"))
      (node (ref "VD13") (pin "2") (pinfunction "Cathode_2") (pintype "passive"))
      (node (ref "VD14") (pin "1") (pinfunction "Anode_1") (pintype "passive"))
      (node (ref "VD16") (pin "1") (pinfunction "Anode_1") (pintype "passive"))
      (node (ref "VD17") (pin "1") (pinfunction "Anode_1") (pintype "passive"))
      (node (ref "VD18") (pin "1") (pinfunction "Anode_1") (pintype "passive"))
      (node (ref "VD19") (pin "1") (pinfunction "Anode_1") (pintype "passive"))
      (node (ref "VD2") (pin "1") (pinfunction "Anode_1") (pintype "passive"))
      (node (ref "VD20") (pin "1") (pinfunction "Anode_1") (pintype "passive"))
      (node (ref "VD21") (pin "3") (pinfunction "COM_3") (pintype "passive"))
      (node (ref "VD3") (pin "1") (pinfunction "Anode_1") (pintype "passive"))
      (node (ref "VD5") (pin "1") (pinfunction "Anode_1") (pintype "passive"))
      (node (ref "VD6") (pin "1") (pinfunction "Anode_1") (pintype "passive"))
      (node (ref "VD7") (pin "1") (pinfunction "Anode_1") (pintype "passive"))
      (node (ref "VD8") (pin "1") (pinfunction "Anode_1") (pintype "passive"))
      (node (ref "VD9") (pin "1") (pinfunction "Anode_1") (pintype "passive"))
      (node (ref "VT1") (pin "2") (pinfunction "Emitter_2") (pintype "passive"))
      (node (ref "VT3") (pin "2") (pinfunction "Source_2") (pintype "passive"))
      (node (ref "VT4") (pin "2") (pinfunction "Emitter_2") (pintype "passive"))
      (node (ref "XP1") (pin "1") (pinfunction "GND_1") (pintype "passive"))
      (node (ref "XP2") (pin "3") (pinfunction "GND_3") (pintype "passive"))
      (node (ref "XS1") (pin "6") (pinfunction "GND_6") (pintype "passive"))
    )
    (net (code "10") (name "INT1") (class "Default")
      (node (ref "DD1") (pin "97") (pinfunction "PE0_97") (pintype "passive"))
      (node (ref "R2") (pin "1") (pinfunction "1_1") (pintype "passive"))
    )
    (net (code "11") (name "MOTOR1 IN1") (class "Default")
      (node (ref "DD1") (pin "23") (pinfunction "PA0_23") (pintype "passive"))
      (node (ref "R63") (pin "1") (pinfunction "1_1") (pintype "passive"))
    )
    (net (code "12") (name "MOTOR1 IN2") (class "Default")
      (node (ref "DD1") (pin "24") (pinfunction "PA1_24") (pintype "passive"))
      (node (ref "R64") (pin "1") (pinfunction "1_1") (pintype "passive"))
    )
    (net (code "13") (name "MOTOR1 OUT1") (class "Default")
      (node (ref "C63") (pin "1") (pinfunction "1_1") (pintype "passive"))
      (node (ref "C64") (pin "2") (pinfunction "2_2") (pintype "passive"))
      (node (ref "DD5") (pin "6") (pinfunction "OUT1_6") (pintype "passive"))
      (node (ref "XS2") (pin "6") (pinfunction "MOTOR1_6") (pintype "passive"))
    )
    (net (code "14") (name "MOTOR1 OUT2") (class "Default")
      (node (ref "C64") (pin "1") (pinfunction "1_1") (pintype "passive"))
      (node (ref "C65") (pin "2") (pinfunction "2_2") (pintype "passive"))
      (node (ref "DD5") (pin "8") (pinfunction "OUT2_8") (pintype "passive"))
      (node (ref "XS2") (pin "7") (pinfunction "MOTOR1_7") (pintype "passive"))
    )
    (net (code "15") (name "MOTOR1 nFAULT") (class "Default")
      (node (ref "DD1") (pin "40") (pinfunction "PE9_40") (pintype "passive"))
      (node (ref "R66") (pin "1") (pinfunction "1_1") (pintype "passive"))
    )
    (net (code "16") (name "MOTOR2 IN1") (class "Default")
      (node (ref "DD1") (pin "25") (pinfunction "PA2_25") (pintype "passive"))
      (node (ref "R81") (pin "1") (pinfunction "1_1") (pintype "passive"))
    )
    (net (code "17") (name "MOTOR2 IN2") (class "Default")
      (node (ref "DD1") (pin "26") (pinfunction "PA3_26") (pintype "passive"))
      (node (ref "R82") (pin "1") (pinfunction "1_1") (pintype "passive"))
    )
    (net (code "18") (name "MOTOR2 OUT1") (class "Default")
      (node (ref "C81") (pin "1") (pinfunction "1_1") (pintype "passive"))
      (node (ref "C82") (pin "2") (pinfunction "2_2") (pintype "passive"))
      (node (ref "DD7") (pin "6") (pinfunction "OUT1_6") (pintype "passive"))
      (node (ref "XS2") (pin "5") (pinfunction "MOTOR2_5") (pintype "passive"))
    )
    (net (code "19") (name "MOTOR2 OUT2") (class "Default")
      (node (ref "C82") (pin "1") (pinfunction "1_1") (pintype "passive"))
      (node (ref "C83") (pin "2") (pinfunction "2_2") (pintype "passive"))
      (node (ref "DD7") (pin "8") (pinfunction "OUT2_8") (pintype "passive"))
      (node (ref "XS2") (pin "8") (pinfunction "MOTOR2_8") (pintype "passive"))
    )
    (net (code "20") (name "MOTOR2 nFAULT") (class "Default")
      (node (ref "DD1") (pin "41") (pinfunction "PE10_41") (pintype "passive"))
      (node (ref "R84") (pin "1") (pinfunction "1_1") (pintype "passive"))
    )
    (net (code "21") (name "MOTOR3 IN1") (class "Default")
      (node (ref "DD1") (pin "31") (pinfunction "PA6_31") (pintype "passive"))
      (node (ref "R86") (pin "1") (pinfunction "1_1") (pintype "passive"))
    )
    (net (code "22") (name "MOTOR3 IN2") (class "Default")
      (node (ref "DD1") (pin "32") (pinfunction "PA7_32") (pintype "passive"))
      (node (ref "R87") (pin "1") (pinfunction "1_1") (pintype "passive"))
    )
    (net (code "23") (name "MOTOR3 OUT1") (class "Default")
      (node (ref "C84") (pin "1") (pinfunction "1_1") (pintype "passive"))
      (node (ref "C85") (pin "2") (pinfunction "2_2") (pintype "passive"))
      (node (ref "DD8") (pin "6") (pinfunction "OUT1_6") (pintype "passive"))
      (node (ref "XS2") (pin "4") (pinfunction "MOTOR3_4") (pintype "passive"))
    )
    (net (code "24") (name "MOTOR3 OUT2") (class "Default")
      (node (ref "C85") (pin "1") (pinfunction "1_1") (pintype "passive"))
      (node (ref "C86") (pin "2") (pinfunction "2_2") (pintype "passive"))
      (node (ref "DD8") (pin "8") (pinfunction "OUT2_8") (pintype "passive"))
      (node (ref "XS2") (pin "9") (pinfunction "MOTOR3_9") (pintype "passive"))
    )
    (net (code "25") (name "MOTOR3 nFAULT") (class "Default")
      (node (ref "DD1") (pin "42") (pinfunction "PE11_42") (pintype "passive"))
      (node (ref "R89") (pin "1") (pinfunction "1_1") (pintype "passive"))
    )
    (net (code "26") (name "MOTOR4 IN1") (class "Default")
      (node (ref "DD1") (pin "59") (pinfunction "PD12_59") (pintype "passive"))
      (node (ref "R91") (pin "1") (pinfunction "1_1") (pintype "passive"))
    )
    (net (code "27") (name "MOTOR4 IN2") (class "Default")
      (node (ref "DD1") (pin "60") (pinfunction "PD13_60") (pintype "passive"))
      (node (ref "R92") (pin "1") (pinfunction "1_1") (pintype "passive"))
    )
    (net (code "28") (name "MOTOR4 OUT1") (class "Default")
      (node (ref "C87") (pin "1") (pinfunction "1_1") (pintype "passive"))
      (node (ref "C88") (pin "2") (pinfunction "2_2") (pintype "passive"))
      (node (ref "DD9") (pin "6") (pinfunction "OUT1_6") (pintype "passive"))
      (node (ref "XS2") (pin "3") (pinfunction "MOTOR4_3") (pintype "passive"))
    )
    (net (code "29") (name "MOTOR4 OUT2") (class "Default")
      (node (ref "C88") (pin "1") (pinfunction "1_1") (pintype "passive"))
      (node (ref "C89") (pin "2") (pinfunction "2_2") (pintype "passive"))
      (node (ref "DD9") (pin "8") (pinfunction "OUT2_8") (pintype "passive"))
      (node (ref "XS2") (pin "10") (pinfunction "MOTOR4_10") (pintype "passive"))
    )
    (net (code "30") (name "MOTOR4 nFAULT") (class "Default")
      (node (ref "DD1") (pin "43") (pinfunction "PE12_43") (pintype "passive"))
      (node (ref "R94") (pin "1") (pinfunction "1_1") (pintype "passive"))
    )
    (net (code "31") (name "MOTOR5 IN1") (class "Default")
      (node (ref "DD1") (pin "61") (pinfunction "PD14_61") (pintype "passive"))
      (node (ref "R96") (pin "1") (pinfunction "1_1") (pintype "passive"))
    )
    (net (code "32") (name "MOTOR5 IN2") (class "Default")
      (node (ref "DD1") (pin "62") (pinfunction "PD15_62") (pintype "passive"))
      (node (ref "R97") (pin "1") (pinfunction "1_1") (pintype "passive"))
    )
    (net (code "33") (name "MOTOR5 OUT1") (class "Default")
      (node (ref "C90") (pin "1") (pinfunction "1_1") (pintype "passive"))
      (node (ref "C91") (pin "2") (pinfunction "2_2") (pintype "passive"))
      (node (ref "DD10") (pin "6") (pinfunction "OUT1_6") (pintype "passive"))
      (node (ref "XS2") (pin "2") (pinfunction "MOTOR5_2") (pintype "passive"))
    )
    (net (code "34") (name "MOTOR5 OUT2") (class "Default")
      (node (ref "C91") (pin "1") (pinfunction "1_1") (pintype "passive"))
      (node (ref "C92") (pin "2") (pinfunction "2_2") (pintype "passive"))
      (node (ref "DD10") (pin "8") (pinfunction "OUT2_8") (pintype "passive"))
      (node (ref "XS2") (pin "11") (pinfunction "MOTOR5_11") (pintype "passive"))
    )
    (net (code "35") (name "MOTOR5 nFAULT") (class "Default")
      (node (ref "DD1") (pin "44") (pinfunction "PE13_44") (pintype "passive"))
      (node (ref "R99") (pin "1") (pinfunction "1_1") (pintype "passive"))
    )
    (net (code "36") (name "MOTOR6 IN1") (class "Default")
      (node (ref "DD1") (pin "63") (pinfunction "PC6_63") (pintype "passive"))
      (node (ref "R76") (pin "1") (pinfunction "1_1") (pintype "passive"))
    )
    (net (code "37") (name "MOTOR6 IN2") (class "Default")
      (node (ref "DD1") (pin "64") (pinfunction "PC7_64") (pintype "passive"))
      (node (ref "R77") (pin "1") (pinfunction "1_1") (pintype "passive"))
    )
    (net (code "38") (name "MOTOR6 OUT1") (class "Default")
      (node (ref "C78") (pin "1") (pinfunction "1_1") (pintype "passive"))
      (node (ref "C79") (pin "2") (pinfunction "2_2") (pintype "passive"))
      (node (ref "DD6") (pin "6") (pinfunction "OUT1_6") (pintype "passive"))
      (node (ref "XS2") (pin "1") (pinfunction "MOTOR6_1") (pintype "passive"))
    )
    (net (code "39") (name "MOTOR6 OUT2") (class "Default")
      (node (ref "C79") (pin "1") (pinfunction "1_1") (pintype "passive"))
      (node (ref "C80") (pin "2") (pinfunction "2_2") (pintype "passive"))
      (node (ref "DD6") (pin "8") (pinfunction "OUT2_8") (pintype "passive"))
      (node (ref "XS2") (pin "12") (pinfunction "MOTOR6_12") (pintype "passive"))
    )
    (net (code "40") (name "MOTOR6 nFAULT") (class "Default")
      (node (ref "DD1") (pin "45") (pinfunction "PE14_45") (pintype "passive"))
      (node (ref "R79") (pin "1") (pinfunction "1_1") (pintype "passive"))
    )
    (net (code "41") (name "MOTOR7 IN1") (class "Default")
      (node (ref "DD1") (pin "65") (pinfunction "PC8_65") (pintype "passive"))
      (node (ref "DD1") (pin "66") (pinfunction "PC9_66") (pintype "passive"))
      (node (ref "R101") (pin "1") (pinfunction "1_1") (pintype "passive"))
    )
    (net (code "42") (name "MOTOR7 IN2") (class "Default")
      (node (ref "R102") (pin "1") (pinfunction "1_1") (pintype "passive"))
    )
    (net (code "43") (name "MOTOR7 OUT1") (class "Default")
      (node (ref "C93") (pin "1") (pinfunction "1_1") (pintype "passive"))
      (node (ref "C94") (pin "2") (pinfunction "2_2") (pintype "passive"))
      (node (ref "DD11") (pin "6") (pinfunction "OUT1_6") (pintype "passive"))
      (node (ref "XS1") (pin "1") (pinfunction "MOTOR7_1") (pintype "passive"))
    )
    (net (code "44") (name "MOTOR7 OUT2") (class "Default")
      (node (ref "C94") (pin "1") (pinfunction "1_1") (pintype "passive"))
      (node (ref "C95") (pin "2") (pinfunction "2_2") (pintype "passive"))
      (node (ref "DD11") (pin "8") (pinfunction "OUT2_8") (pintype "passive"))
      (node (ref "XS1") (pin "12") (pinfunction "MOTOR7_12") (pintype "passive"))
    )
    (net (code "45") (name "MOTOR7 nFAULT") (class "Default")
      (node (ref "DD1") (pin "46") (pinfunction "PE15_46") (pintype "passive"))
      (node (ref "R104") (pin "1") (pinfunction "1_1") (pintype "passive"))
    )
    (net (code "46") (name "Net-(A1-GND-Pad22)") (class "Default")
      (node (ref "A1") (pin "22") (pinfunction "GND_22") (pintype "passive"))
      (node (ref "R19") (pin "2") (pinfunction "2_2") (pintype "passive"))
    )
    (net (code "47") (name "Net-(A1-PIO1)") (class "Default")
      (node (ref "A1") (pin "24") (pinfunction "PIO1_24") (pintype "passive"))
      (node (ref "R15") (pin "2") (pinfunction "2_2") (pintype "passive"))
    )
    (net (code "48") (name "Net-(A1-PIO3)") (class "Default")
      (node (ref "A1") (pin "26") (pinfunction "PIO3_26") (pintype "passive"))
      (node (ref "R17") (pin "2") (pinfunction "2_2") (pintype "passive"))
      (node (ref "R18") (pin "2") (pinfunction "2_2") (pintype "passive"))
    )
    (net (code "49") (name "Net-(A1-RESET)") (class "Default")
      (node (ref "A1") (pin "11") (pinfunction "RESET_11") (pintype "passive"))
      (node (ref "R1") (pin "2") (pinfunction "2_2") (pintype "passive"))
      (node (ref "R5") (pin "1") (pinfunction "1_1") (pintype "passive"))
    )
    (net (code "50") (name "Net-(A1-RXD)") (class "Default")
      (node (ref "A1") (pin "2") (pinfunction "RXD_2") (pintype "passive"))
      (node (ref "L3") (pin "2") (pinfunction "2_2") (pintype "passive"))
    )
    (net (code "51") (name "Net-(A1-TXD)") (class "Default")
      (node (ref "A1") (pin "1") (pinfunction "TXD_1") (pintype "passive"))
      (node (ref "L2") (pin "2") (pinfunction "2_2") (pintype "passive"))
    )
    (net (code "52") (name "Net-(A2-AD0)") (class "Default")
      (node (ref "A2") (pin "9") (pinfunction "AD0_9") (pintype "passive"))
      (node (ref "R7") (pin "2") (pinfunction "2_2") (pintype "passive"))
    )
    (net (code "53") (name "Net-(A2-INT1)") (class "Default")
      (node (ref "A2") (pin "12") (pinfunction "INT1_12") (pintype "passive"))
      (node (ref "R2") (pin "2") (pinfunction "2_2") (pintype "passive"))
    )
    (net (code "54") (name "Net-(A2-REGOUT)") (class "Default")
      (node (ref "A2") (pin "10") (pinfunction "REGOUT_10") (pintype "passive"))
      (node (ref "C5") (pin "2") (pinfunction "2_2") (pintype "passive"))
    )
    (net (code "55") (name "Net-(A2-RESV-Pad20)") (class "Default")
      (node (ref "A2") (pin "20") (pinfunction "RESV_20") (pintype "passive"))
      (node (ref "C11") (pin "1") (pinfunction "1_1") (pintype "passive"))
    )
    (net (code "56") (name "Net-(A2-SCL)") (class "Default")
      (node (ref "A2") (pin "23") (pinfunction "SCL_23") (pintype "passive"))
      (node (ref "R3") (pin "2") (pinfunction "2_2") (pintype "passive"))
      (node (ref "R6") (pin "1") (pinfunction "1_1") (pintype "passive"))
    )
    (net (code "57") (name "Net-(A2-SDA)") (class "Default")
      (node (ref "A2") (pin "24") (pinfunction "SDA_24") (pintype "passive"))
      (node (ref "R4") (pin "2") (pinfunction "2_2") (pintype "passive"))
      (node (ref "R8") (pin "1") (pinfunction "1_1") (pintype "passive"))
    )
    (net (code "58") (name "Net-(C6-Pad2)") (class "Default")
      (node (ref "C6") (pin "2") (pinfunction "2_2") (pintype "passive"))
      (node (ref "R10") (pin "1") (pinfunction "1_1") (pintype "passive"))
      (node (ref "R13") (pin "1") (pinfunction "1_1") (pintype "passive"))
      (node (ref "R9") (pin "2") (pinfunction "2_2") (pintype "passive"))
    )
    (net (code "59") (name "Net-(C7-Pad2)") (class "Default")
      (node (ref "C7") (pin "2") (pinfunction "2_2") (pintype "passive"))
      (node (ref "R11") (pin "2") (pinfunction "2_2") (pintype "passive"))
      (node (ref "R12") (pin "1") (pinfunction "1_1") (pintype "passive"))
      (node (ref "R14") (pin "1") (pinfunction "1_1") (pintype "passive"))
    )
    (net (code "60") (name "Net-(C30-Pad2)") (class "Default")
      (node (ref "C30") (pin "2") (pinfunction "2_2") (pintype "passive"))
      (node (ref "R26") (pin "2") (pinfunction "2_2") (pintype "passive"))
      (node (ref "R28") (pin "1") (pinfunction "1_1") (pintype "passive"))
      (node (ref "R31") (pin "1") (pinfunction "1_1") (pintype "passive"))
    )
    (net (code "61") (name "Net-(C31-Pad2)") (class "Default")
      (node (ref "C31") (pin "2") (pinfunction "2_2") (pintype "passive"))
      (node (ref "R27") (pin "2") (pinfunction "2_2") (pintype "passive"))
      (node (ref "R30") (pin "1") (pinfunction "1_1") (pintype "passive"))
      (node (ref "R32") (pin "1") (pinfunction "1_1") (pintype "passive"))
    )
    (net (code "62") (name "Net-(C55-Pad1)") (class "Default")
      (node (ref "C55") (pin "1") (pinfunction "1_1") (pintype "passive"))
      (node (ref "R60") (pin "1") (pinfunction "1_1") (pintype "passive"))
      (node (ref "R68") (pin "1") (pinfunction "1_1") (pintype "passive"))
      (node (ref "U1") (pin "2") (pinfunction "2_2") (pintype "passive"))
    )
    (net (code "63") (name "Net-(C55-Pad2)") (class "Default")
      (node (ref "C55") (pin "2") (pinfunction "2_2") (pintype "passive"))
      (node (ref "L6") (pin "2") (pinfunction "2_2") (pintype "passive"))
      (node (ref "L8") (pin "1") (pinfunction "1_1") (pintype "passive"))
      (node (ref "R68") (pin "2") (pinfunction "2_2") (pintype "passive"))
      (node (ref "U1") (pin "1") (pinfunction "1_1") (pintype "passive"))
    )
    (net (code "64") (name "Net-(C56-Pad1)") (class "Default")
      (node (ref "C56") (pin "1") (pinfunction "1_1") (pintype "passive"))
      (node (ref "R61") (pin "1") (pinfunction "1_1") (pintype "passive"))
      (node (ref "R69") (pin "1") (pinfunction "1_1") (pintype "passive"))
      (node (ref "U2") (pin "2") (pinfunction "2_2") (pintype "passive"))
    )
    (net (code "65") (name "Net-(C56-Pad2)") (class "Default")
      (node (ref "C56") (pin "2") (pinfunction "2_2") (pintype "passive"))
      (node (ref "L7") (pin "2") (pinfunction "2_2") (pintype "passive"))
      (node (ref "L9") (pin "1") (pinfunction "1_1") (pintype "passive"))
      (node (ref "R69") (pin "2") (pinfunction "2_2") (pintype "passive"))
      (node (ref "U2") (pin "1") (pinfunction "1_1") (pintype "passive"))
    )
    (net (code "66") (name "Net-(DA1-IN+)") (class "Default")
      (node (ref "DA1") (pin "1") (pinfunction "IN+_1") (pintype "passive"))
      (node (ref "DA1") (pin "4") (pinfunction "OUT_4") (pintype "passive"))
      (node (ref "R22") (pin "1") (pinfunction "1_1") (pintype "passive"))
    )
    (net (code "67") (name "Net-(DA1-IN-)") (class "Default")
      (node (ref "DA1") (pin "3") (pinfunction "IN-_3") (pintype "passive"))
      (node (ref "R13") (pin "2") (pinfunction "2_2") (pintype "passive"))
      (node (ref "VD2") (pin "2") (pinfunction "Cathode_2") (pintype "passive"))
    )
    (net (code "68") (name "Net-(DA2-IN+)") (class "Default")
      (node (ref "DA2") (pin "1") (pinfunction "IN+_1") (pintype "passive"))
      (node (ref "DA2") (pin "4") (pinfunction "OUT_4") (pintype "passive"))
      (node (ref "R23") (pin "1") (pinfunction "1_1") (pintype "passive"))
    )
    (net (code "69") (name "Net-(DA2-IN-)") (class "Default")
      (node (ref "DA2") (pin "3") (pinfunction "IN-_3") (pintype "passive"))
      (node (ref "R14") (pin "2") (pinfunction "2_2") (pintype "passive"))
      (node (ref "VD3") (pin "2") (pinfunction "Cathode_2") (pintype "passive"))
    )
    (net (code "70") (name "Net-(DA3-FILTER)") (class "Default")
      (node (ref "C14") (pin "2") (pinfunction "2_2") (pintype "passive"))
      (node (ref "DA3") (pin "1") (pinfunction "FILTER_1") (pintype "passive"))
    )
    (net (code "71") (name "Net-(DA3-OUTF)") (class "Default")
      (node (ref "C27") (pin "2") (pinfunction "2_2") (pintype "passive"))
      (node (ref "C28") (pin "2") (pinfunction "2_2") (pintype "passive"))
      (node (ref "C34") (pin "2") (pinfunction "2_2") (pintype "passive"))
      (node (ref "C35") (pin "2") (pinfunction "2_2") (pintype "passive"))
      (node (ref "DA3") (pin "5") (pinfunction "OUTS_5") (pintype "passive"))
      (node (ref "DA3") (pin "6") (pinfunction "OUTF_6") (pintype "passive"))
      (node (ref "DD1") (pin "21") (pinfunction "VREF+_21") (pintype "passive"))
      (node (ref "VD13") (pin "1") (pinfunction "Anode_1") (pintype "passive"))
    )
    (net (code "72") (name "Net-(DA4-BOOT)") (class "Default")
      (node (ref "C32") (pin "1") (pinfunction "1_1") (pintype "passive"))
      (node (ref "DA4") (pin "1") (pinfunction "BOOT_1") (pintype "passive"))
    )
    (net (code "73") (name "Net-(DA4-PH)") (class "Default")
      (node (ref "C32") (pin "2") (pinfunction "2_2") (pintype "passive"))
      (node (ref "DA4") (pin "8") (pinfunction "PH_8") (pintype "passive"))
      (node (ref "L5") (pin "1") (pinfunction "1_1") (pintype "passive"))
      (node (ref "VD9") (pin "2") (pinfunction "Cathode_2") (pintype "passive"))
    )
    (net (code "74") (name "Net-(DA4-VSENSE)") (class "Default")
      (node (ref "DA4") (pin "4") (pinfunction "VSENSE_4") (pintype "passive"))
      (node (ref "R34") (pin "2") (pinfunction "2_2") (pintype "passive"))
      (node (ref "R36") (pin "1") (pinfunction "1_1") (pintype "passive"))
    )
    (net (code "75") (name "Net-(DA5-Ct)") (class "Default")
      (node (ref "DA5") (pin "4") (pinfunction "Ct_4") (pintype "passive"))
      (node (ref "R25") (pin "1") (pinfunction "1_1") (pintype "passive"))
    )
    (net (code "76") (name "Net-(DA5-MR)") (class "Default")
      (node (ref "DA5") (pin "3") (pinfunction "MR_3") (pintype "passive"))
      (node (ref "R24") (pin "2") (pinfunction "2_2") (pintype "passive"))
    )
    (net (code "77") (name "Net-(DA5-RESET)") (class "Default")
      (node (ref "DA5") (pin "1") (pinfunction "RESET_1") (pintype "passive"))
      (node (ref "DD1") (pin "14") (pinfunction "NRST_14") (pintype "passive"))
      (node (ref "R35") (pin "1") (pinfunction "1_1") (pintype "passive"))
      (node (ref "XP2") (pin "5") (pinfunction "RST_5") (pintype "passive"))
    )
    (net (code "78") (name "Net-(DA6-Anode)") (class "Default")
      (node (ref "DA6") (pin "3") (pinfunction "Anode_3") (pintype "passive"))
      (node (ref "R29") (pin "1") (pinfunction "1_1") (pintype "passive"))
    )
    (net (code "79") (name "Net-(DA7-IN+)") (class "Default")
      (node (ref "DA7") (pin "1") (pinfunction "IN+_1") (pintype "passive"))
      (node (ref "DA7") (pin "4") (pinfunction "OUT_4") (pintype "passive"))
      (node (ref "R39") (pin "1") (pinfunction "1_1") (pintype "passive"))
    )
    (net (code "80") (name "Net-(DA7-IN-)") (class "Default")
      (node (ref "DA7") (pin "3") (pinfunction "IN-_3") (pintype "passive"))
      (node (ref "R31") (pin "2") (pinfunction "2_2") (pintype "passive"))
      (node (ref "VD10") (pin "2") (pinfunction "Cathode_2") (pintype "passive"))
    )
    (net (code "81") (name "Net-(DA8-IN+)") (class "Default")
      (node (ref "DA8") (pin "1") (pinfunction "IN+_1") (pintype "passive"))
      (node (ref "DA8") (pin "4") (pinfunction "OUT_4") (pintype "passive"))
      (node (ref "R40") (pin "1") (pinfunction "1_1") (pintype "passive"))
    )
    (net (code "82") (name "Net-(DA8-IN-)") (class "Default")
      (node (ref "DA8") (pin "3") (pinfunction "IN-_3") (pintype "passive"))
      (node (ref "R32") (pin "2") (pinfunction "2_2") (pintype "passive"))
      (node (ref "VD11") (pin "2") (pinfunction "Cathode_2") (pintype "passive"))
    )
    (net (code "83") (name "Net-(DD1-BOOT0)") (class "Default")
      (node (ref "DD1") (pin "94") (pinfunction "BOOT0_94") (pintype "passive"))
      (node (ref "R37") (pin "2") (pinfunction "2_2") (pintype "passive"))
    )
    (net (code "84") (name "Net-(DD1-BOOT1)") (class "Default")
      (node (ref "DD1") (pin "37") (pinfunction "BOOT1_37") (pintype "passive"))
      (node (ref "R38") (pin "2") (pinfunction "2_2") (pintype "passive"))
    )
    (net (code "85") (name "Net-(DD1-OSCI)") (class "Default")
      (node (ref "C24") (pin "2") (pinfunction "2_2") (pintype "passive"))
      (node (ref "DD1") (pin "12") (pinfunction "OSCI_12") (pintype "passive"))
      (node (ref "R33") (pin "2") (pinfunction "2_2") (pintype "passive"))
      (node (ref "ZQ1") (pin "5") (pinfunction "Anode_5") (pintype "passive"))
    )
    (net (code "86") (name "Net-(DD1-OSCO)") (class "Default")
      (node (ref "C25") (pin "2") (pinfunction "2_2") (pintype "passive"))
      (node (ref "DD1") (pin "13") (pinfunction "OSCO_13") (pintype "passive"))
      (node (ref "R33") (pin "1") (pinfunction "1_1") (pintype "passive"))
      (node (ref "ZQ1") (pin "4") (pinfunction "Anode_4") (pintype "passive"))
    )
    (net (code "87") (name "Net-(DD1-PA11)") (class "Default")
      (node (ref "DD1") (pin "70") (pinfunction "PA11_70") (pintype "passive"))
      (node (ref "R45") (pin "1") (pinfunction "1_1") (pintype "passive"))
    )
    (net (code "88") (name "Net-(DD1-PA12)") (class "Default")
      (node (ref "DD1") (pin "71") (pinfunction "PA12_71") (pintype "passive"))
      (node (ref "R46") (pin "1") (pinfunction "1_1") (pintype "passive"))
    )
    (net (code "89") (name "Net-(DD1-PA13)") (class "Default")
      (node (ref "DD1") (pin "72") (pinfunction "PA13_72") (pintype "passive"))
      (node (ref "XP2") (pin "1") (pinfunction "SWC_1") (pintype "passive"))
    )
    (net (code "90") (name "Net-(DD1-PA14)") (class "Default")
      (node (ref "DD1") (pin "76") (pinfunction "PA14_76") (pintype "passive"))
      (node (ref "XP2") (pin "2") (pinfunction "SWD_2") (pintype "passive"))
    )
    (net (code "91") (name "Net-(DD1-PB10)") (class "Default")
      (node (ref "DD1") (pin "47") (pinfunction "PB10_47") (pintype "passive"))
      (node (ref "R41") (pin "1") (pinfunction "1_1") (pintype "passive"))
    )
    (net (code "92") (name "Net-(DD1-PB11)") (class "Default")
      (node (ref "DD1") (pin "48") (pinfunction "PB11_48") (pintype "passive"))
      (node (ref "R42") (pin "1") (pinfunction "1_1") (pintype "passive"))
    )
    (net (code "93") (name "Net-(DD1-PB12)") (class "Default")
      (node (ref "DD1") (pin "51") (pinfunction "PB12_51") (pintype "passive"))
      (node (ref "R50") (pin "1") (pinfunction "1_1") (pintype "passive"))
    )
    (net (code "94") (name "Net-(DD1-PB13)") (class "Default")
      (node (ref "DD1") (pin "52") (pinfunction "PB13_52") (pintype "passive"))
      (node (ref "R51") (pin "1") (pinfunction "1_1") (pintype "passive"))
    )
    (net (code "95") (name "Net-(DD1-PB14)") (class "Default")
      (node (ref "DD1") (pin "53") (pinfunction "PB14_53") (pintype "passive"))
      (node (ref "R52") (pin "1") (pinfunction "1_1") (pintype "passive"))
    )
    (net (code "96") (name "Net-(DD1-PB15)") (class "Default")
      (node (ref "DD1") (pin "54") (pinfunction "PB15_54") (pintype "passive"))
      (node (ref "R53") (pin "1") (pinfunction "1_1") (pintype "passive"))
    )
    (net (code "97") (name "Net-(DD1-PC1)") (class "Default")
      (node (ref "C19") (pin "2") (pinfunction "2_2") (pintype "passive"))
      (node (ref "DD1") (pin "16") (pinfunction "PC1_16") (pintype "passive"))
      (node (ref "R22") (pin "2") (pinfunction "2_2") (pintype "passive"))
      (node (ref "VD7") (pin "2") (pinfunction "Cathode_2") (pintype "passive"))
    )
    (net (code "98") (name "Net-(DD1-PC2)") (class "Default")
      (node (ref "C23") (pin "2") (pinfunction "2_2") (pintype "passive"))
      (node (ref "DD1") (pin "17") (pinfunction "PC2_17") (pintype "passive"))
      (node (ref "R29") (pin "2") (pinfunction "2_2") (pintype "passive"))
      (node (ref "VD12") (pin "2") (pinfunction "Cathode_2") (pintype "passive"))
    )
    (net (code "99") (name "Net-(DD1-PC3)") (class "Default")
      (node (ref "C20") (pin "2") (pinfunction "2_2") (pintype "passive"))
      (node (ref "DD1") (pin "18") (pinfunction "PC3_18") (pintype "passive"))
      (node (ref "R23") (pin "2") (pinfunction "2_2") (pintype "passive"))
      (node (ref "VD8") (pin "2") (pinfunction "Cathode_2") (pintype "passive"))
    )
    (net (code "100") (name "Net-(DD1-PD8)") (class "Default")
      (node (ref "DD1") (pin "55") (pinfunction "PD8_55") (pintype "passive"))
      (node (ref "R54") (pin "1") (pinfunction "1_1") (pintype "passive"))
    )
    (net (code "101") (name "Net-(DD1-PE1)") (class "Default")
      (node (ref "DD1") (pin "98") (pinfunction "PE1_98") (pintype "passive"))
      (node (ref "R24") (pin "1") (pinfunction "1_1") (pintype "passive"))
    )
    (net (code "102") (name "Net-(DD1-PE2)") (class "Default")
      (node (ref "DD1") (pin "1") (pinfunction "PE2_1") (pintype "passive"))
      (node (ref "R44") (pin "2") (pinfunction "2_2") (pintype "passive"))
    )
    (net (code "103") (name "Net-(DD2-SCL)") (class "Default")
      (node (ref "DD2") (pin "6") (pinfunction "SCL_6") (pintype "passive"))
      (node (ref "R41") (pin "2") (pinfunction "2_2") (pintype "passive"))
      (node (ref "R43") (pin "1") (pinfunction "1_1") (pintype "passive"))
    )
    (net (code "104") (name "Net-(DD2-SDA)") (class "Default")
      (node (ref "DD2") (pin "5") (pinfunction "SDA_5") (pintype "passive"))
      (node (ref "R42") (pin "2") (pinfunction "2_2") (pintype "passive"))
      (node (ref "R47") (pin "1") (pinfunction "1_1") (pintype "passive"))
    )
    (net (code "105") (name "Net-(DD3-CANH)") (class "Default")
      (node (ref "DD3") (pin "7") (pinfunction "CANH_7") (pintype "passive"))
      (node (ref "L10") (pin "1") (pinfunction "1_1") (pintype "passive"))
      (node (ref "R59") (pin "2") (pinfunction "2_2") (pintype "passive"))
    )
    (net (code "106") (name "Net-(DD3-CANL)") (class "Default")
      (node (ref "DD3") (pin "6") (pinfunction "CANL_6") (pintype "passive"))
      (node (ref "L10") (pin "2") (pinfunction "2_2") (pintype "passive"))
      (node (ref "R58") (pin "2") (pinfunction "2_2") (pintype "passive"))
    )
    (net (code "107") (name "Net-(DD3-D)") (class "Default")
      (node (ref "DD3") (pin "1") (pinfunction "D_1") (pintype "passive"))
      (node (ref "R45") (pin "2") (pinfunction "2_2") (pintype "passive"))
    )
    (net (code "108") (name "Net-(DD3-R)") (class "Default")
      (node (ref "DD3") (pin "4") (pinfunction "R_4") (pintype "passive"))
      (node (ref "R46") (pin "2") (pinfunction "2_2") (pintype "passive"))
    )
    (net (code "109") (name "Net-(DD3-Rs)") (class "Default")
      (node (ref "DD3") (pin "8") (pinfunction "Rs_8") (pintype "passive"))
      (node (ref "R55") (pin "2") (pinfunction "2_2") (pintype "passive"))
    )
    (net (code "110") (name "Net-(DD3-Vref)") (class "Default")
      (node (ref "C53") (pin "2") (pinfunction "2_2") (pintype "passive"))
      (node (ref "DD3") (pin "5") (pinfunction "Vref_5") (pintype "passive"))
      (node (ref "R58") (pin "1") (pinfunction "1_1") (pintype "passive"))
      (node (ref "R59") (pin "1") (pinfunction "1_1") (pintype "passive"))
    )
    (net (code "111") (name "Net-(DD4-CLK)") (class "Default")
      (node (ref "DD4") (pin "6") (pinfunction "CLK_6") (pintype "passive"))
      (node (ref "R51") (pin "2") (pinfunction "2_2") (pintype "passive"))
    )
    (net (code "112") (name "Net-(DD4-DI)") (class "Default")
      (node (ref "DD4") (pin "5") (pinfunction "DI_5") (pintype "passive"))
      (node (ref "R53") (pin "2") (pinfunction "2_2") (pintype "passive"))
    )
    (net (code "113") (name "Net-(DD4-DO)") (class "Default")
      (node (ref "DD4") (pin "2") (pinfunction "DO_2") (pintype "passive"))
      (node (ref "R52") (pin "2") (pinfunction "2_2") (pintype "passive"))
    )
    (net (code "114") (name "Net-(DD4-{slash}CS)") (class "Default")
      (node (ref "DD4") (pin "1") (pinfunction "/CS_1") (pintype "passive"))
      (node (ref "R50") (pin "2") (pinfunction "2_2") (pintype "passive"))
      (node (ref "R62") (pin "1") (pinfunction "1_1") (pintype "passive"))
    )
    (net (code "115") (name "Net-(DD4-{slash}RESET)") (class "Default")
      (node (ref "DD4") (pin "7") (pinfunction "/RESET_7") (pintype "passive"))
      (node (ref "R70") (pin "1") (pinfunction "1_1") (pintype "passive"))
    )
    (net (code "116") (name "Net-(DD4-{slash}WP)") (class "Default")
      (node (ref "DD4") (pin "3") (pinfunction "/WP_3") (pintype "passive"))
      (node (ref "R54") (pin "2") (pinfunction "2_2") (pintype "passive"))
      (node (ref "R57") (pin "1") (pinfunction "1_1") (pintype "passive"))
    )
    (net (code "117") (name "Net-(DD5-IN1)") (class "Default")
      (node (ref "DD5") (pin "3") (pinfunction "IN1_3") (pintype "passive"))
      (node (ref "R63") (pin "2") (pinfunction "2_2") (pintype "passive"))
    )
    (net (code "118") (name "Net-(DD5-IN2)") (class "Default")
      (node (ref "DD5") (pin "2") (pinfunction "IN2_2") (pintype "passive"))
      (node (ref "R64") (pin "2") (pinfunction "2_2") (pintype "passive"))
    )
    (net (code "119") (name "Net-(DD5-ISEN)") (class "Default")
      (node (ref "DD5") (pin "7") (pinfunction "ISEN_7") (pintype "passive"))
      (node (ref "R67") (pin "2") (pinfunction "2_2") (pintype "passive"))
    )
    (net (code "120") (name "Net-(DD5-nFAULT)") (class "Default")
      (node (ref "DD5") (pin "4") (pinfunction "nFAULT_4") (pintype "passive"))
      (node (ref "R65") (pin "2") (pinfunction "2_2") (pintype "passive"))
      (node (ref "R66") (pin "2") (pinfunction "2_2") (pintype "passive"))
    )
    (net (code "121") (name "Net-(DD6-IN1)") (class "Default")
      (node (ref "DD6") (pin "3") (pinfunction "IN1_3") (pintype "passive"))
      (node (ref "R76") (pin "2") (pinfunction "2_2") (pintype "passive"))
    )
    (net (code "122") (name "Net-(DD6-IN2)") (class "Default")
      (node (ref "DD6") (pin "2") (pinfunction "IN2_2") (pintype "passive"))
      (node (ref "R77") (pin "2") (pinfunction "2_2") (pintype "passive"))
    )
    (net (code "123") (name "Net-(DD6-ISEN)") (class "Default")
      (node (ref "DD6") (pin "7") (pinfunction "ISEN_7") (pintype "passive"))
      (node (ref "R80") (pin "2") (pinfunction "2_2") (pintype "passive"))
    )
    (net (code "124") (name "Net-(DD6-nFAULT)") (class "Default")
      (node (ref "DD6") (pin "4") (pinfunction "nFAULT_4") (pintype "passive"))
      (node (ref "R78") (pin "2") (pinfunction "2_2") (pintype "passive"))
      (node (ref "R79") (pin "2") (pinfunction "2_2") (pintype "passive"))
    )
    (net (code "125") (name "Net-(DD7-IN1)") (class "Default")
      (node (ref "DD7") (pin "3") (pinfunction "IN1_3") (pintype "passive"))
      (node (ref "R81") (pin "2") (pinfunction "2_2") (pintype "passive"))
    )
    (net (code "126") (name "Net-(DD7-IN2)") (class "Default")
      (node (ref "DD7") (pin "2") (pinfunction "IN2_2") (pintype "passive"))
      (node (ref "R82") (pin "2") (pinfunction "2_2") (pintype "passive"))
    )
    (net (code "127") (name "Net-(DD7-ISEN)") (class "Default")
      (node (ref "DD7") (pin "7") (pinfunction "ISEN_7") (pintype "passive"))
      (node (ref "R85") (pin "2") (pinfunction "2_2") (pintype "passive"))
    )
    (net (code "128") (name "Net-(DD7-nFAULT)") (class "Default")
      (node (ref "DD7") (pin "4") (pinfunction "nFAULT_4") (pintype "passive"))
      (node (ref "R83") (pin "2") (pinfunction "2_2") (pintype "passive"))
      (node (ref "R84") (pin "2") (pinfunction "2_2") (pintype "passive"))
    )
    (net (code "129") (name "Net-(DD8-IN1)") (class "Default")
      (node (ref "DD8") (pin "3") (pinfunction "IN1_3") (pintype "passive"))
      (node (ref "R86") (pin "2") (pinfunction "2_2") (pintype "passive"))
    )
    (net (code "130") (name "Net-(DD8-IN2)") (class "Default")
      (node (ref "DD8") (pin "2") (pinfunction "IN2_2") (pintype "passive"))
      (node (ref "R87") (pin "2") (pinfunction "2_2") (pintype "passive"))
    )
    (net (code "131") (name "Net-(DD8-ISEN)") (class "Default")
      (node (ref "DD8") (pin "7") (pinfunction "ISEN_7") (pintype "passive"))
      (node (ref "R90") (pin "2") (pinfunction "2_2") (pintype "passive"))
    )
    (net (code "132") (name "Net-(DD8-nFAULT)") (class "Default")
      (node (ref "DD8") (pin "4") (pinfunction "nFAULT_4") (pintype "passive"))
      (node (ref "R88") (pin "2") (pinfunction "2_2") (pintype "passive"))
      (node (ref "R89") (pin "2") (pinfunction "2_2") (pintype "passive"))
    )
    (net (code "133") (name "Net-(DD9-IN1)") (class "Default")
      (node (ref "DD9") (pin "3") (pinfunction "IN1_3") (pintype "passive"))
      (node (ref "R91") (pin "2") (pinfunction "2_2") (pintype "passive"))
    )
    (net (code "134") (name "Net-(DD9-IN2)") (class "Default")
      (node (ref "DD9") (pin "2") (pinfunction "IN2_2") (pintype "passive"))
      (node (ref "R92") (pin "2") (pinfunction "2_2") (pintype "passive"))
    )
    (net (code "135") (name "Net-(DD9-ISEN)") (class "Default")
      (node (ref "DD9") (pin "7") (pinfunction "ISEN_7") (pintype "passive"))
      (node (ref "R95") (pin "2") (pinfunction "2_2") (pintype "passive"))
    )
    (net (code "136") (name "Net-(DD9-nFAULT)") (class "Default")
      (node (ref "DD9") (pin "4") (pinfunction "nFAULT_4") (pintype "passive"))
      (node (ref "R93") (pin "2") (pinfunction "2_2") (pintype "passive"))
      (node (ref "R94") (pin "2") (pinfunction "2_2") (pintype "passive"))
    )
    (net (code "137") (name "Net-(DD10-IN1)") (class "Default")
      (node (ref "DD10") (pin "3") (pinfunction "IN1_3") (pintype "passive"))
      (node (ref "R96") (pin "2") (pinfunction "2_2") (pintype "passive"))
    )
    (net (code "138") (name "Net-(DD10-IN2)") (class "Default")
      (node (ref "DD10") (pin "2") (pinfunction "IN2_2") (pintype "passive"))
      (node (ref "R97") (pin "2") (pinfunction "2_2") (pintype "passive"))
    )
    (net (code "139") (name "Net-(DD10-ISEN)") (class "Default")
      (node (ref "DD10") (pin "7") (pinfunction "ISEN_7") (pintype "passive"))
      (node (ref "R100") (pin "2") (pinfunction "2_2") (pintype "passive"))
    )
    (net (code "140") (name "Net-(DD10-nFAULT)") (class "Default")
      (node (ref "DD10") (pin "4") (pinfunction "nFAULT_4") (pintype "passive"))
      (node (ref "R98") (pin "2") (pinfunction "2_2") (pintype "passive"))
      (node (ref "R99") (pin "2") (pinfunction "2_2") (pintype "passive"))
    )
    (net (code "141") (name "Net-(DD11-IN1)") (class "Default")
      (node (ref "DD11") (pin "3") (pinfunction "IN1_3") (pintype "passive"))
      (node (ref "R101") (pin "2") (pinfunction "2_2") (pintype "passive"))
    )
    (net (code "142") (name "Net-(DD11-IN2)") (class "Default")
      (node (ref "DD11") (pin "2") (pinfunction "IN2_2") (pintype "passive"))
      (node (ref "R102") (pin "2") (pinfunction "2_2") (pintype "passive"))
    )
    (net (code "143") (name "Net-(DD11-ISEN)") (class "Default")
      (node (ref "DD11") (pin "7") (pinfunction "ISEN_7") (pintype "passive"))
      (node (ref "R105") (pin "2") (pinfunction "2_2") (pintype "passive"))
    )
    (net (code "144") (name "Net-(DD11-nFAULT)") (class "Default")
      (node (ref "DD11") (pin "4") (pinfunction "nFAULT_4") (pintype "passive"))
      (node (ref "R103") (pin "2") (pinfunction "2_2") (pintype "passive"))
      (node (ref "R104") (pin "2") (pinfunction "2_2") (pintype "passive"))
    )
    (net (code "145") (name "Net-(HL1-Cathode)") (class "Default")
      (node (ref "HL1") (pin "2") (pinfunction "Cathode_2") (pintype "passive"))
      (node (ref "R20") (pin "2") (pinfunction "2_2") (pintype "passive"))
    )
    (net (code "146") (name "Net-(HL2-Cathode)") (class "Default")
      (node (ref "HL2") (pin "2") (pinfunction "Cathode_2") (pintype "passive"))
      (node (ref "R48") (pin "1") (pinfunction "1_1") (pintype "passive"))
    )
    (net (code "147") (name "Net-(HL3-Cathode)") (class "Default")
      (node (ref "HL3") (pin "2") (pinfunction "Cathode_2") (pintype "passive"))
      (node (ref "R56") (pin "1") (pinfunction "1_1") (pintype "passive"))
    )
    (net (code "148") (name "Net-(L1-Pad2)") (class "Default")
      (node (ref "L1") (pin "2") (pinfunction "2_2") (pintype "passive"))
      (node (ref "R1") (pin "1") (pinfunction "1_1") (pintype "passive"))
    )
    (net (code "149") (name "Net-(R71-Pad2)") (class "Default")
      (node (ref "R71") (pin "2") (pinfunction "2_2") (pintype "passive"))
      (node (ref "R73") (pin "1") (pinfunction "1_1") (pintype "passive"))
      (node (ref "U1") (pin "4") (pinfunction "4_4") (pintype "passive"))
    )
    (net (code "150") (name "Net-(R72-Pad2)") (class "Default")
      (node (ref "R72") (pin "2") (pinfunction "2_2") (pintype "passive"))
      (node (ref "R74") (pin "1") (pinfunction "1_1") (pintype "passive"))
      (node (ref "U2") (pin "4") (pinfunction "4_4") (pintype "passive"))
    )
    (net (code "151") (name "Net-(VD4-Anode)") (class "Default")
      (node (ref "C9") (pin "2") (pinfunction "2_2") (pintype "passive"))
      (node (ref "R16") (pin "2") (pinfunction "2_2") (pintype "passive"))
      (node (ref "VD4") (pin "1") (pinfunction "Anode_1") (pintype "passive"))
      (node (ref "VT2") (pin "1") (pinfunction "Gate_1") (pintype "passive"))
      (node (ref "VT3") (pin "1") (pinfunction "Gate_1") (pintype "passive"))
    )
    (net (code "152") (name "Net-(VT1-Base)") (class "Default")
      (node (ref "R15") (pin "1") (pinfunction "1_1") (pintype "passive"))
      (node (ref "R21") (pin "2") (pinfunction "2_2") (pintype "passive"))
      (node (ref "VT1") (pin "1") (pinfunction "Base_1") (pintype "passive"))
    )
    (net (code "153") (name "Net-(VT1-Collector)") (class "Default")
      (node (ref "R20") (pin "1") (pinfunction "1_1") (pintype "passive"))
      (node (ref "VT1") (pin "3") (pinfunction "Collector_3") (pintype "passive"))
    )
    (net (code "154") (name "Net-(VT2-Drain)") (class "Default")
      (node (ref "C8") (pin "2") (pinfunction "2_2") (pintype "passive"))
      (node (ref "L4") (pin "4") (pinfunction "4_4") (pintype "passive"))
      (node (ref "VT2") (pin "3") (pinfunction "Drain_3") (pintype "passive"))
    )
    (net (code "155") (name "Net-(VT4-Base)") (class "Default")
      (node (ref "R44") (pin "1") (pinfunction "1_1") (pintype "passive"))
      (node (ref "R49") (pin "2") (pinfunction "2_2") (pintype "passive"))
      (node (ref "VT4") (pin "1") (pinfunction "Base_1") (pintype "passive"))
    )
    (net (code "156") (name "Net-(VT4-Collector)") (class "Default")
      (node (ref "R48") (pin "2") (pinfunction "2_2") (pintype "passive"))
      (node (ref "VT4") (pin "3") (pinfunction "Collector_3") (pintype "passive"))
    )
    (net (code "157") (name "PIO3") (class "Default")
      (node (ref "DD1") (pin "2") (pinfunction "PE3_2") (pintype "passive"))
      (node (ref "R18") (pin "1") (pinfunction "1_1") (pintype "passive"))
    )
    (net (code "158") (name "SCL") (class "Default")
      (node (ref "DD1") (pin "92") (pinfunction "PB6_92") (pintype "passive"))
      (node (ref "R3") (pin "1") (pinfunction "1_1") (pintype "passive"))
    )
    (net (code "159") (name "SDA") (class "Default")
      (node (ref "DD1") (pin "93") (pinfunction "PB7_93") (pintype "passive"))
      (node (ref "R4") (pin "1") (pinfunction "1_1") (pintype "passive"))
    )
    (net (code "160") (name "SENSOR11 IN") (class "Default")
      (node (ref "R60") (pin "2") (pinfunction "2_2") (pintype "passive"))
      (node (ref "VD19") (pin "2") (pinfunction "Cathode_2") (pintype "passive"))
      (node (ref "XS1") (pin "4") (pinfunction "SENSOR1_4") (pintype "passive"))
    )
    (net (code "161") (name "SENSOR11 OUT") (class "Default")
      (node (ref "DD1") (pin "35") (pinfunction "PB0_35") (pintype "passive"))
      (node (ref "R73") (pin "2") (pinfunction "2_2") (pintype "passive"))
    )
    (net (code "162") (name "SENSOR12 IN") (class "Default")
      (node (ref "R61") (pin "2") (pinfunction "2_2") (pintype "passive"))
      (node (ref "VD20") (pin "2") (pinfunction "Cathode_2") (pintype "passive"))
      (node (ref "XS1") (pin "5") (pinfunction "SENSOR2_5") (pintype "passive"))
    )
    (net (code "163") (name "SENSOR12 OUT") (class "Default")
      (node (ref "DD1") (pin "36") (pinfunction "PB1_36") (pintype "passive"))
      (node (ref "R74") (pin "2") (pinfunction "2_2") (pintype "passive"))
    )
    (net (code "164") (name "SENSOR21 IN") (class "Default")
      (node (ref "C21") (pin "2") (pinfunction "2_2") (pintype "passive"))
      (node (ref "R26") (pin "1") (pinfunction "1_1") (pintype "passive"))
      (node (ref "VD5") (pin "2") (pinfunction "Cathode_2") (pintype "passive"))
      (node (ref "XS1") (pin "8") (pinfunction "SENSOR3_8") (pintype "passive"))
    )
    (net (code "165") (name "SENSOR21 OUT") (class "Default")
      (node (ref "C48") (pin "2") (pinfunction "2_2") (pintype "passive"))
      (node (ref "DD1") (pin "33") (pinfunction "PC4_33") (pintype "passive"))
      (node (ref "R39") (pin "2") (pinfunction "2_2") (pintype "passive"))
      (node (ref "VD16") (pin "2") (pinfunction "Cathode_2") (pintype "passive"))
    )
    (net (code "166") (name "SENSOR22 IN") (class "Default")
      (node (ref "C22") (pin "2") (pinfunction "2_2") (pintype "passive"))
      (node (ref "R27") (pin "1") (pinfunction "1_1") (pintype "passive"))
      (node (ref "VD6") (pin "2") (pinfunction "Cathode_2") (pintype "passive"))
      (node (ref "XS1") (pin "9") (pinfunction "SENSOR4_9") (pintype "passive"))
    )
    (net (code "167") (name "SENSOR22 OUT") (class "Default")
      (node (ref "C50") (pin "2") (pinfunction "2_2") (pintype "passive"))
      (node (ref "DD1") (pin "34") (pinfunction "PC5_34") (pintype "passive"))
      (node (ref "R40") (pin "2") (pinfunction "2_2") (pintype "passive"))
      (node (ref "VD17") (pin "2") (pinfunction "Cathode_2") (pintype "passive"))
    )
    (net (code "168") (name "VCC SENSOR") (class "Default")
      (node (ref "FU1") (pin "2") (pinfunction "2_2") (pintype "passive"))
      (node (ref "FU2") (pin "2") (pinfunction "2_2") (pintype "passive"))
      (node (ref "XS1") (pin "7") (pinfunction "+5V_7") (pintype "passive"))
    )
    (net (code "169") (name "VIN+") (class "Default")
      (node (ref "C4") (pin "1") (pinfunction "1_1") (pintype "passive"))
      (node (ref "L4") (pin "1") (pinfunction "1_1") (pintype "passive"))
      (node (ref "RU1") (pin "1") (pinfunction "1_1") (pintype "passive"))
      (node (ref "VD1") (pin "2") (pinfunction "2_2") (pintype "passive"))
      (node (ref "XS1") (pin "10") (pinfunction "VIN_10") (pintype "passive"))
    )
    (net (code "170") (name "VIN-") (class "Default")
      (node (ref "C4") (pin "2") (pinfunction "2_2") (pintype "passive"))
      (node (ref "L4") (pin "2") (pinfunction "2_2") (pintype "passive"))
      (node (ref "RU1") (pin "2") (pinfunction "2_2") (pintype "passive"))
      (node (ref "VD1") (pin "1") (pinfunction "1_1") (pintype "passive"))
      (node (ref "XS1") (pin "11") (pinfunction "GND_11") (pintype "passive"))
    )
    (net (code "171") (name "unconnected-(A1-AI0-Pad9)") (class "Default")
      (node (ref "A1") (pin "9") (pinfunction "AI0_9") (pintype "passive"))
    )
    (net (code "172") (name "unconnected-(A1-AI1-Pad10)") (class "Default")
      (node (ref "A1") (pin "10") (pinfunction "AI1_10") (pintype "passive"))
    )
    (net (code "173") (name "unconnected-(A1-CLK-Pad5)") (class "Default")
      (node (ref "A1") (pin "5") (pinfunction "CLK_5") (pintype "passive"))
    )
    (net (code "174") (name "unconnected-(A1-CLK-Pad19)") (class "Default")
      (node (ref "A1") (pin "19") (pinfunction "CLK_19") (pintype "passive"))
    )
    (net (code "175") (name "unconnected-(A1-CSB-Pad16)") (class "Default")
      (node (ref "A1") (pin "16") (pinfunction "CSB_16") (pintype "passive"))
    )
    (net (code "176") (name "unconnected-(A1-CTS-Pad3)") (class "Default")
      (node (ref "A1") (pin "3") (pinfunction "CTS_3") (pintype "passive"))
    )
    (net (code "177") (name "unconnected-(A1-D+-Pad20)") (class "Default")
      (node (ref "A1") (pin "20") (pinfunction "D+_20") (pintype "passive"))
    )
    (net (code "178") (name "unconnected-(A1-D--Pad14)") (class "Default")
      (node (ref "A1") (pin "14") (pinfunction "D-_14") (pintype "passive"))
    )
    (net (code "179") (name "unconnected-(A1-IN-Pad7)") (class "Default")
      (node (ref "A1") (pin "7") (pinfunction "IN_7") (pintype "passive"))
    )
    (net (code "180") (name "unconnected-(A1-MISO-Pad18)") (class "Default")
      (node (ref "A1") (pin "18") (pinfunction "MISO_18") (pintype "passive"))
    )
    (net (code "181") (name "unconnected-(A1-MOSI-Pad17)") (class "Default")
      (node (ref "A1") (pin "17") (pinfunction "MOSI_17") (pintype "passive"))
    )
    (net (code "182") (name "unconnected-(A1-NC-Pad14)") (class "Default")
      (node (ref "A1") (pin "14") (pinfunction "NC_14") (pintype "passive"))
    )
    (net (code "183") (name "unconnected-(A1-OUT-Pad6)") (class "Default")
      (node (ref "A1") (pin "6") (pinfunction "OUT_6") (pintype "passive"))
    )
    (net (code "184") (name "unconnected-(A1-PIO0-Pad23)") (class "Default")
      (node (ref "A1") (pin "23") (pinfunction "PIO0_23") (pintype "passive"))
    )
    (net (code "185") (name "unconnected-(A1-PIO2-Pad25)") (class "Default")
      (node (ref "A1") (pin "25") (pinfunction "PIO2_25") (pintype "passive"))
    )
    (net (code "186") (name "unconnected-(A1-PIO4-Pad27)") (class "Default")
      (node (ref "A1") (pin "27") (pinfunction "PIO4_27") (pintype "passive"))
    )
    (net (code "187") (name "unconnected-(A1-PIO5-Pad28)") (class "Default")
      (node (ref "A1") (pin "28") (pinfunction "PIO5_28") (pintype "passive"))
    )
    (net (code "188") (name "unconnected-(A1-PIO6-Pad29)") (class "Default")
      (node (ref "A1") (pin "29") (pinfunction "PIO6_29") (pintype "passive"))
    )
    (net (code "189") (name "unconnected-(A1-PIO7-Pad30)") (class "Default")
      (node (ref "A1") (pin "30") (pinfunction "PIO7_30") (pintype "passive"))
    )
    (net (code "190") (name "unconnected-(A1-PIO8-Pad31)") (class "Default")
      (node (ref "A1") (pin "31") (pinfunction "PIO8_31") (pintype "passive"))
    )
    (net (code "191") (name "unconnected-(A1-PIO9-Pad32)") (class "Default")
      (node (ref "A1") (pin "32") (pinfunction "PIO9_32") (pintype "passive"))
    )
    (net (code "192") (name "unconnected-(A1-PIO10-Pad33)") (class "Default")
      (node (ref "A1") (pin "33") (pinfunction "PIO10_33") (pintype "passive"))
    )
    (net (code "193") (name "unconnected-(A1-PIO11-Pad34)") (class "Default")
      (node (ref "A1") (pin "34") (pinfunction "PIO11_34") (pintype "passive"))
    )
    (net (code "194") (name "unconnected-(A1-RTS-Pad4)") (class "Default")
      (node (ref "A1") (pin "4") (pinfunction "RTS_4") (pintype "passive"))
    )
    (net (code "195") (name "unconnected-(A1-SYNC-Pad8)") (class "Default")
      (node (ref "A1") (pin "8") (pinfunction "SYNC_8") (pintype "passive"))
    )
    (net (code "196") (name "unconnected-(A2-AUX_CL-Pad7)") (class "Default")
      (node (ref "A2") (pin "7") (pinfunction "AUX_CL_7") (pintype "passive"))
    )
    (net (code "197") (name "unconnected-(A2-AUX_DA-Pad21)") (class "Default")
      (node (ref "A2") (pin "21") (pinfunction "AUX_DA_21") (pintype "passive"))
    )
    (net (code "198") (name "unconnected-(A2-CS-Pad22)") (class "Default")
      (node (ref "A2") (pin "22") (pinfunction "CS_22") (pintype "passive"))
    )
    (net (code "199") (name "unconnected-(A2-NC-Pad2)") (class "Default")
      (node (ref "A2") (pin "2") (pinfunction "NC_2") (pintype "passive"))
    )
    (net (code "200") (name "unconnected-(A2-NC-Pad3)") (class "Default")
      (node (ref "A2") (pin "3") (pinfunction "NC_3") (pintype "passive"))
    )
    (net (code "201") (name "unconnected-(A2-NC-Pad4)") (class "Default")
      (node (ref "A2") (pin "4") (pinfunction "NC_4") (pintype "passive"))
    )
    (net (code "202") (name "unconnected-(A2-NC-Pad5)") (class "Default")
      (node (ref "A2") (pin "5") (pinfunction "NC_5") (pintype "passive"))
    )
    (net (code "203") (name "unconnected-(A2-NC-Pad6)") (class "Default")
      (node (ref "A2") (pin "6") (pinfunction "NC_6") (pintype "passive"))
    )
    (net (code "204") (name "unconnected-(A2-NC-Pad14)") (class "Default")
      (node (ref "A2") (pin "14") (pinfunction "NC_14") (pintype "passive"))
    )
    (net (code "205") (name "unconnected-(A2-NC-Pad15)") (class "Default")
      (node (ref "A2") (pin "15") (pinfunction "NC_15") (pintype "passive"))
    )
    (net (code "206") (name "unconnected-(A2-NC-Pad16)") (class "Default")
      (node (ref "A2") (pin "16") (pinfunction "NC_16") (pintype "passive"))
    )
    (net (code "207") (name "unconnected-(A2-NC-Pad17)") (class "Default")
      (node (ref "A2") (pin "17") (pinfunction "NC_17") (pintype "passive"))
    )
    (net (code "208") (name "unconnected-(A2-RESV-Pad19)") (class "Default")
      (node (ref "A2") (pin "19") (pinfunction "RESV_19") (pintype "passive"))
    )
    (net (code "209") (name "unconnected-(DA4-ENA-Pad5)") (class "Default")
      (node (ref "DA4") (pin "5") (pinfunction "ENA_5") (pintype "passive"))
    )
    (net (code "210") (name "unconnected-(DA4-NC-Pad2)") (class "Default")
      (node (ref "DA4") (pin "2") (pinfunction "NC_2") (pintype "passive"))
    )
    (net (code "211") (name "unconnected-(DA4-NC-Pad3)") (class "Default")
      (node (ref "DA4") (pin "3") (pinfunction "NC_3") (pintype "passive"))
    )
    (net (code "212") (name "unconnected-(DD1-NC-Pad73)") (class "Default")
      (node (ref "DD1") (pin "73") (pinfunction "NC_73") (pintype "passive"))
    )
    (net (code "213") (name "unconnected-(DD1-PA4-Pad29)") (class "Default")
      (node (ref "DD1") (pin "29") (pinfunction "PA4_29") (pintype "passive"))
    )
    (net (code "214") (name "unconnected-(DD1-PA5-Pad30)") (class "Default")
      (node (ref "DD1") (pin "30") (pinfunction "PA5_30") (pintype "passive"))
    )
    (net (code "215") (name "unconnected-(DD1-PA8-Pad67)") (class "Default")
      (node (ref "DD1") (pin "67") (pinfunction "PA8_67") (pintype "passive"))
    )
    (net (code "216") (name "unconnected-(DD1-PA9-Pad68)") (class "Default")
      (node (ref "DD1") (pin "68") (pinfunction "PA9_68") (pintype "passive"))
    )
    (net (code "217") (name "unconnected-(DD1-PA10-Pad69)") (class "Default")
      (node (ref "DD1") (pin "69") (pinfunction "PA10_69") (pintype "passive"))
    )
    (net (code "218") (name "unconnected-(DD1-PA15-Pad77)") (class "Default")
      (node (ref "DD1") (pin "77") (pinfunction "PA15_77") (pintype "passive"))
    )
    (net (code "219") (name "unconnected-(DD1-PB3-Pad89)") (class "Default")
      (node (ref "DD1") (pin "89") (pinfunction "PB3_89") (pintype "passive"))
    )
    (net (code "220") (name "unconnected-(DD1-PB4-Pad90)") (class "Default")
      (node (ref "DD1") (pin "90") (pinfunction "PB4_90") (pintype "passive"))
    )
    (net (code "221") (name "unconnected-(DD1-PB5-Pad91)") (class "Default")
      (node (ref "DD1") (pin "91") (pinfunction "PB5_91") (pintype "passive"))
    )
    (net (code "222") (name "unconnected-(DD1-PB8-Pad95)") (class "Default")
      (node (ref "DD1") (pin "95") (pinfunction "PB8_95") (pintype "passive"))
    )
    (net (code "223") (name "unconnected-(DD1-PB9-Pad96)") (class "Default")
      (node (ref "DD1") (pin "96") (pinfunction "PB9_96") (pintype "passive"))
    )
    (net (code "224") (name "unconnected-(DD1-PC0-Pad15)") (class "Default")
      (node (ref "DD1") (pin "15") (pinfunction "PC0_15") (pintype "passive"))
    )
    (net (code "225") (name "unconnected-(DD1-PC12-Pad80)") (class "Default")
      (node (ref "DD1") (pin "80") (pinfunction "PC12_80") (pintype "passive"))
    )
    (net (code "226") (name "unconnected-(DD1-PC13-Pad7)") (class "Default")
      (node (ref "DD1") (pin "7") (pinfunction "PC13_7") (pintype "passive"))
    )
    (net (code "227") (name "unconnected-(DD1-PC14-Pad8)") (class "Default")
      (node (ref "DD1") (pin "8") (pinfunction "PC14_8") (pintype "passive"))
    )
    (net (code "228") (name "unconnected-(DD1-PC15-Pad9)") (class "Default")
      (node (ref "DD1") (pin "9") (pinfunction "PC15_9") (pintype "passive"))
    )
    (net (code "229") (name "unconnected-(DD1-PD0-Pad81)") (class "Default")
      (node (ref "DD1") (pin "81") (pinfunction "PD0_81") (pintype "passive"))
    )
    (net (code "230") (name "unconnected-(DD1-PD1-Pad82)") (class "Default")
      (node (ref "DD1") (pin "82") (pinfunction "PD1_82") (pintype "passive"))
    )
    (net (code "231") (name "unconnected-(DD1-PD2-Pad83)") (class "Default")
      (node (ref "DD1") (pin "83") (pinfunction "PD2_83") (pintype "passive"))
    )
    (net (code "232") (name "unconnected-(DD1-PD3-Pad84)") (class "Default")
      (node (ref "DD1") (pin "84") (pinfunction "PD3_84") (pintype "passive"))
    )
    (net (code "233") (name "unconnected-(DD1-PD4-Pad85)") (class "Default")
      (node (ref "DD1") (pin "85") (pinfunction "PD4_85") (pintype "passive"))
    )
    (net (code "234") (name "unconnected-(DD1-PD5-Pad86)") (class "Default")
      (node (ref "DD1") (pin "86") (pinfunction "PD5_86") (pintype "passive"))
    )
    (net (code "235") (name "unconnected-(DD1-PD6-Pad87)") (class "Default")
      (node (ref "DD1") (pin "87") (pinfunction "PD6_87") (pintype "passive"))
    )
    (net (code "236") (name "unconnected-(DD1-PD7-Pad88)") (class "Default")
      (node (ref "DD1") (pin "88") (pinfunction "PD7_88") (pintype "passive"))
    )
    (net (code "237") (name "unconnected-(DD1-PD9-Pad56)") (class "Default")
      (node (ref "DD1") (pin "56") (pinfunction "PD9_56") (pintype "passive"))
    )
    (net (code "238") (name "unconnected-(DD1-PD10-Pad57)") (class "Default")
      (node (ref "DD1") (pin "57") (pinfunction "PD10_57") (pintype "passive"))
    )
    (net (code "239") (name "unconnected-(DD1-PD11-Pad58)") (class "Default")
      (node (ref "DD1") (pin "58") (pinfunction "PD11_58") (pintype "passive"))
    )
    (net (code "240") (name "unconnected-(DD1-PE5-Pad4)") (class "Default")
      (node (ref "DD1") (pin "4") (pinfunction "PE5_4") (pintype "passive"))
    )
    (net (code "241") (name "unconnected-(DD1-PE6-Pad5)") (class "Default")
      (node (ref "DD1") (pin "5") (pinfunction "PE6_5") (pintype "passive"))
    )
    (net (code "242") (name "unconnected-(DD1-PE7-Pad38)") (class "Default")
      (node (ref "DD1") (pin "38") (pinfunction "PE7_38") (pintype "passive"))
    )
    (net (code "243") (name "unconnected-(DD1-PE8-Pad39)") (class "Default")
      (node (ref "DD1") (pin "39") (pinfunction "PE8_39") (pintype "passive"))
    )
    (net (code "244") (name "unconnected-(L7-Pad1)") (class "Default")
      (node (ref "L7") (pin "1") (pinfunction "1_1") (pintype "passive"))
    )
  )
)
